# 2_waffling80-MX_matrix.net
KiCad netlist of a schematic drawn in Altium Designer
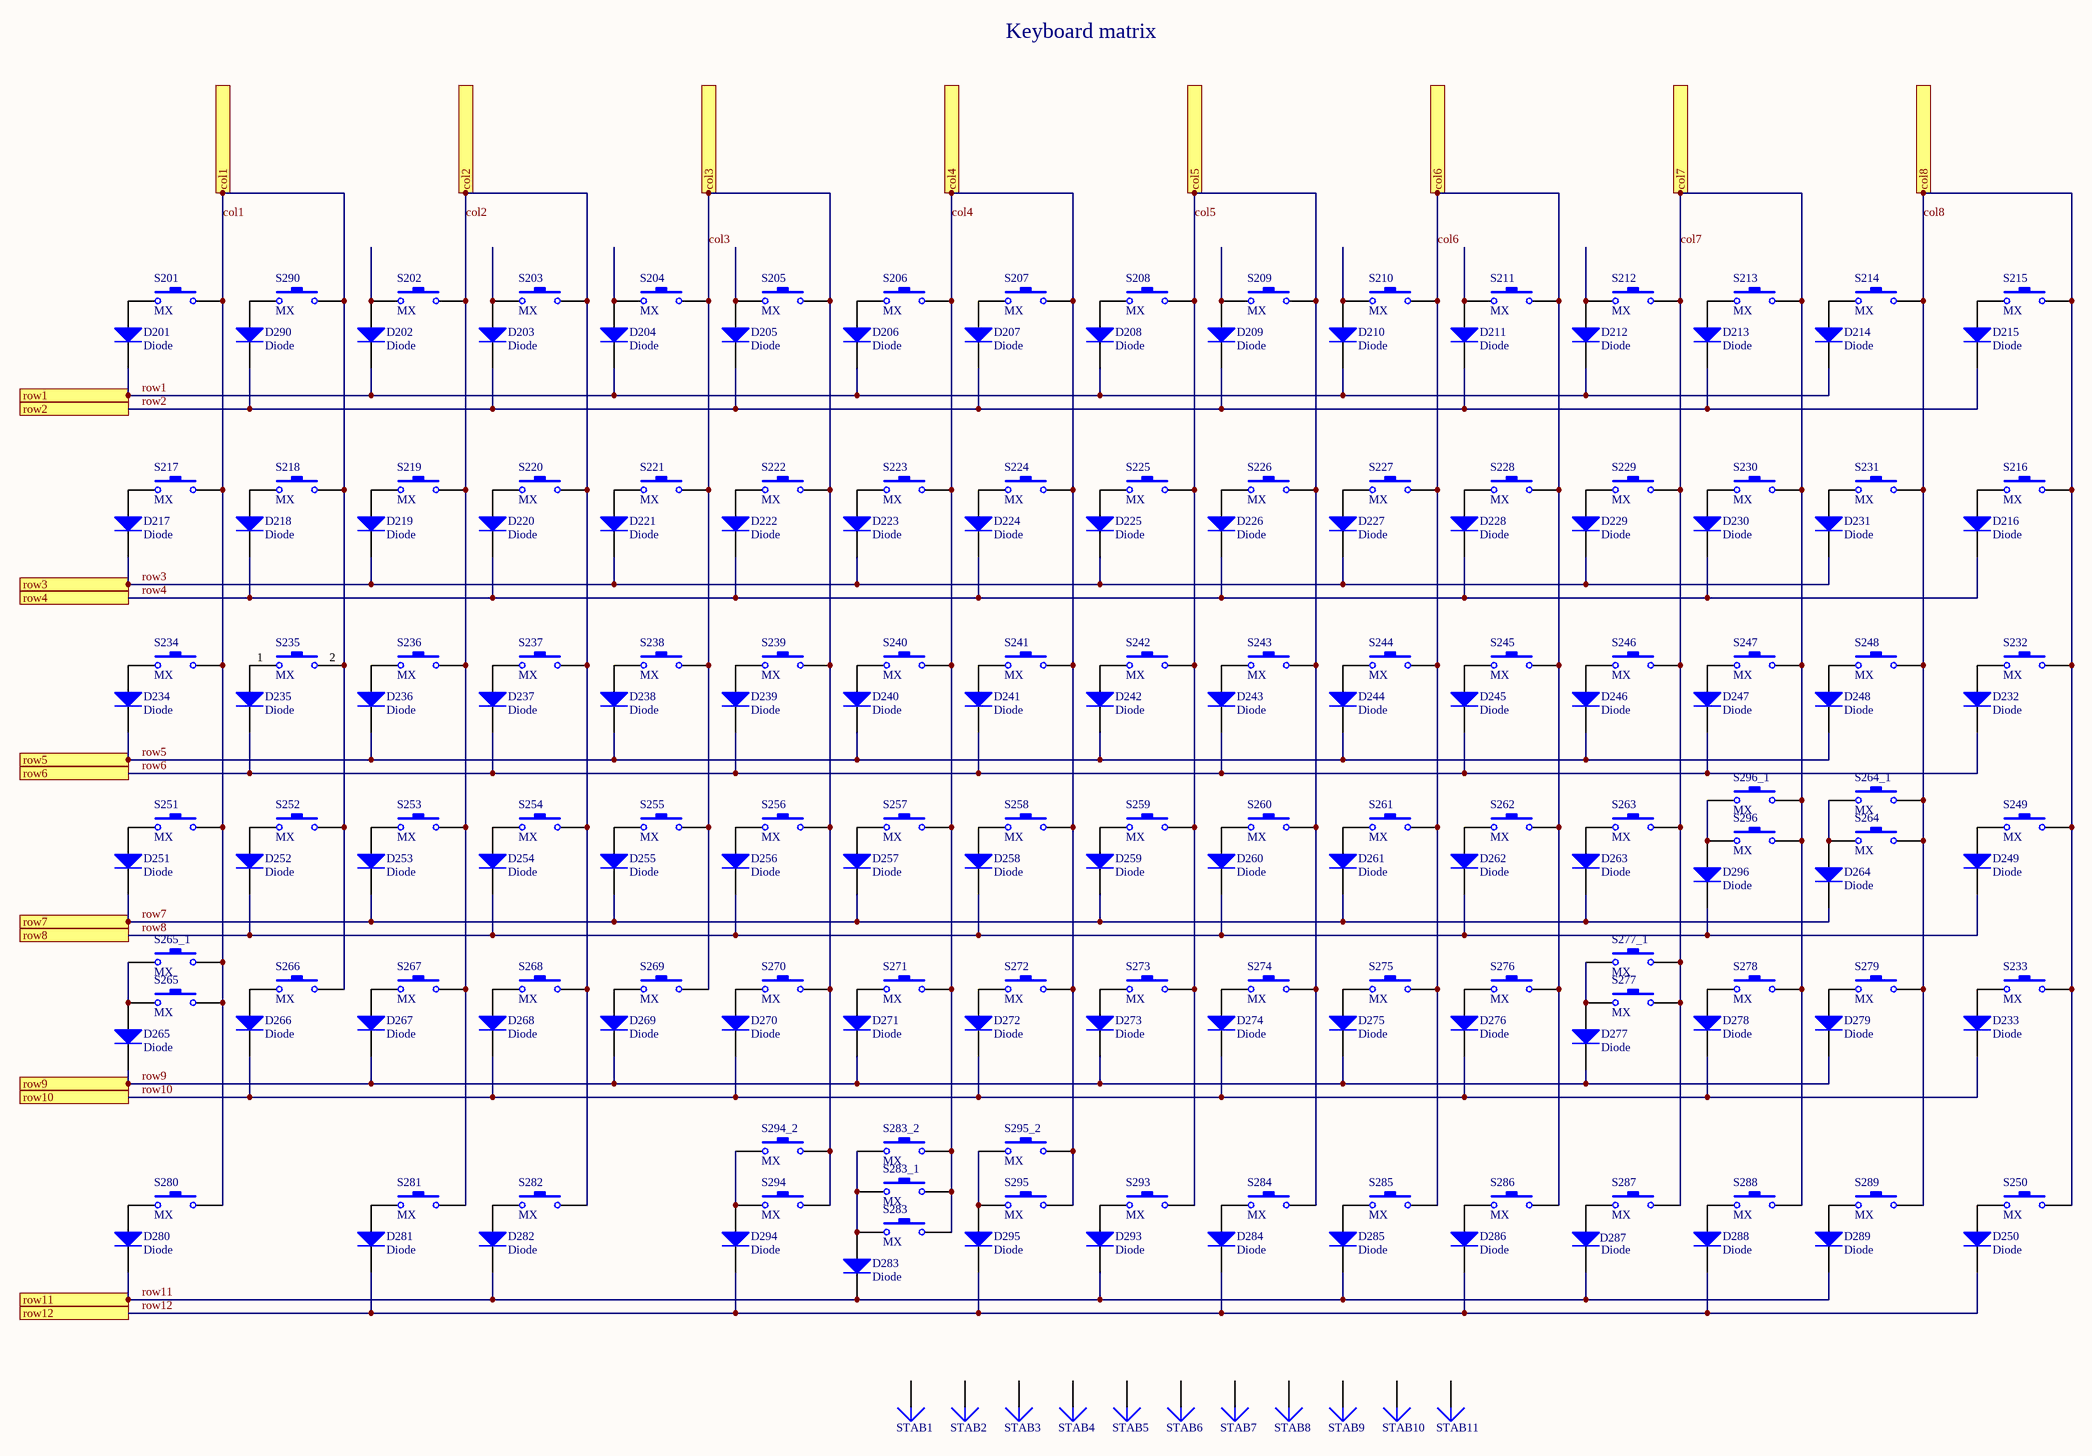
[diagram p0: 2_waffling80-MX_matrix.SchDoc]

(export (version "E")
  (design (tool "Eeschema 10.0.6"))
  (components
    (comp (ref "D201")
      (value "Diode")
      (footprint "SOD-123")
      (description "Default Diode")
      (fields (field (name "LCSC PART #") "C81598") (field (name "MRF.PART") "1N4148W"))
      (libsource (lib "Miscellaneous Devices") (part "Diode"))
    )
    (comp (ref "D202")
      (value "Diode")
      (footprint "SOD-123")
      (description "Default Diode")
      (fields (field (name "LCSC PART #") "C81598") (field (name "MRF.PART") "1N4148W"))
      (libsource (lib "Miscellaneous Devices") (part "Diode"))
    )
    (comp (ref "D203")
      (value "Diode")
      (footprint "SOD-123")
      (description "Default Diode")
      (fields (field (name "LCSC PART #") "C81598") (field (name "MRF.PART") "1N4148W"))
      (libsource (lib "Miscellaneous Devices") (part "Diode"))
    )
    (comp (ref "D204")
      (value "Diode")
      (footprint "SOD-123")
      (description "Default Diode")
      (fields (field (name "LCSC PART #") "C81598") (field (name "MRF.PART") "1N4148W"))
      (libsource (lib "Miscellaneous Devices") (part "Diode"))
    )
    (comp (ref "D205")
      (value "Diode")
      (footprint "SOD-123")
      (description "Default Diode")
      (fields (field (name "LCSC PART #") "C81598") (field (name "MRF.PART") "1N4148W"))
      (libsource (lib "Miscellaneous Devices") (part "Diode"))
    )
    (comp (ref "D206")
      (value "Diode")
      (footprint "SOD-123")
      (description "Default Diode")
      (fields (field (name "LCSC PART #") "C81598") (field (name "MRF.PART") "1N4148W"))
      (libsource (lib "Miscellaneous Devices") (part "Diode"))
    )
    (comp (ref "D207")
      (value "Diode")
      (footprint "SOD-123")
      (description "Default Diode")
      (fields (field (name "LCSC PART #") "C81598") (field (name "MRF.PART") "1N4148W"))
      (libsource (lib "Miscellaneous Devices") (part "Diode"))
    )
    (comp (ref "D208")
      (value "Diode")
      (footprint "SOD-123")
      (description "Default Diode")
      (fields (field (name "LCSC PART #") "C81598") (field (name "MRF.PART") "1N4148W"))
      (libsource (lib "Miscellaneous Devices") (part "Diode"))
    )
    (comp (ref "D209")
      (value "Diode")
      (footprint "SOD-123")
      (description "Default Diode")
      (fields (field (name "LCSC PART #") "C81598") (field (name "MRF.PART") "1N4148W"))
      (libsource (lib "Miscellaneous Devices") (part "Diode"))
    )
    (comp (ref "D210")
      (value "Diode")
      (footprint "SOD-123")
      (description "Default Diode")
      (fields (field (name "LCSC PART #") "C81598") (field (name "MRF.PART") "1N4148W"))
      (libsource (lib "Miscellaneous Devices") (part "Diode"))
    )
    (comp (ref "D211")
      (value "Diode")
      (footprint "SOD-123")
      (description "Default Diode")
      (fields (field (name "LCSC PART #") "C81598") (field (name "MRF.PART") "1N4148W"))
      (libsource (lib "Miscellaneous Devices") (part "Diode"))
    )
    (comp (ref "D212")
      (value "Diode")
      (footprint "SOD-123")
      (description "Default Diode")
      (fields (field (name "LCSC PART #") "C81598") (field (name "MRF.PART") "1N4148W"))
      (libsource (lib "Miscellaneous Devices") (part "Diode"))
    )
    (comp (ref "D213")
      (value "Diode")
      (footprint "SOD-123")
      (description "Default Diode")
      (fields (field (name "LCSC PART #") "C81598") (field (name "MRF.PART") "1N4148W"))
      (libsource (lib "Miscellaneous Devices") (part "Diode"))
    )
    (comp (ref "D214")
      (value "Diode")
      (footprint "SOD-123")
      (description "Default Diode")
      (fields (field (name "LCSC PART #") "C81598") (field (name "MRF.PART") "1N4148W"))
      (libsource (lib "Miscellaneous Devices") (part "Diode"))
    )
    (comp (ref "D215")
      (value "Diode")
      (footprint "SOD-123")
      (description "Default Diode")
      (fields (field (name "LCSC PART #") "C81598") (field (name "MRF.PART") "1N4148W"))
      (libsource (lib "Miscellaneous Devices") (part "Diode"))
    )
    (comp (ref "D216")
      (value "Diode")
      (footprint "SOD-123")
      (description "Default Diode")
      (fields (field (name "LCSC PART #") "C81598") (field (name "MRF.PART") "1N4148W"))
      (libsource (lib "Miscellaneous Devices") (part "Diode"))
    )
    (comp (ref "D217")
      (value "Diode")
      (footprint "SOD-123")
      (description "Default Diode")
      (fields (field (name "LCSC PART #") "C81598") (field (name "MRF.PART") "1N4148W"))
      (libsource (lib "Miscellaneous Devices") (part "Diode"))
    )
    (comp (ref "D218")
      (value "Diode")
      (footprint "SOD-123")
      (description "Default Diode")
      (fields (field (name "LCSC PART #") "C81598") (field (name "MRF.PART") "1N4148W"))
      (libsource (lib "Miscellaneous Devices") (part "Diode"))
    )
    (comp (ref "D219")
      (value "Diode")
      (footprint "SOD-123")
      (description "Default Diode")
      (fields (field (name "LCSC PART #") "C81598") (field (name "MRF.PART") "1N4148W"))
      (libsource (lib "Miscellaneous Devices") (part "Diode"))
    )
    (comp (ref "D220")
      (value "Diode")
      (footprint "SOD-123")
      (description "Default Diode")
      (fields (field (name "LCSC PART #") "C81598") (field (name "MRF.PART") "1N4148W"))
      (libsource (lib "Miscellaneous Devices") (part "Diode"))
    )
    (comp (ref "D221")
      (value "Diode")
      (footprint "SOD-123")
      (description "Default Diode")
      (fields (field (name "LCSC PART #") "C81598") (field (name "MRF.PART") "1N4148W"))
      (libsource (lib "Miscellaneous Devices") (part "Diode"))
    )
    (comp (ref "D222")
      (value "Diode")
      (footprint "SOD-123")
      (description "Default Diode")
      (fields (field (name "LCSC PART #") "C81598") (field (name "MRF.PART") "1N4148W"))
      (libsource (lib "Miscellaneous Devices") (part "Diode"))
    )
    (comp (ref "D223")
      (value "Diode")
      (footprint "SOD-123")
      (description "Default Diode")
      (fields (field (name "LCSC PART #") "C81598") (field (name "MRF.PART") "1N4148W"))
      (libsource (lib "Miscellaneous Devices") (part "Diode"))
    )
    (comp (ref "D224")
      (value "Diode")
      (footprint "SOD-123")
      (description "Default Diode")
      (fields (field (name "LCSC PART #") "C81598") (field (name "MRF.PART") "1N4148W"))
      (libsource (lib "Miscellaneous Devices") (part "Diode"))
    )
    (comp (ref "D225")
      (value "Diode")
      (footprint "SOD-123")
      (description "Default Diode")
      (fields (field (name "LCSC PART #") "C81598") (field (name "MRF.PART") "1N4148W"))
      (libsource (lib "Miscellaneous Devices") (part "Diode"))
    )
    (comp (ref "D226")
      (value "Diode")
      (footprint "SOD-123")
      (description "Default Diode")
      (fields (field (name "LCSC PART #") "C81598") (field (name "MRF.PART") "1N4148W"))
      (libsource (lib "Miscellaneous Devices") (part "Diode"))
    )
    (comp (ref "D227")
      (value "Diode")
      (footprint "SOD-123")
      (description "Default Diode")
      (fields (field (name "LCSC PART #") "C81598") (field (name "MRF.PART") "1N4148W"))
      (libsource (lib "Miscellaneous Devices") (part "Diode"))
    )
    (comp (ref "D228")
      (value "Diode")
      (footprint "SOD-123")
      (description "Default Diode")
      (fields (field (name "LCSC PART #") "C81598") (field (name "MRF.PART") "1N4148W"))
      (libsource (lib "Miscellaneous Devices") (part "Diode"))
    )
    (comp (ref "D229")
      (value "Diode")
      (footprint "SOD-123")
      (description "Default Diode")
      (fields (field (name "LCSC PART #") "C81598") (field (name "MRF.PART") "1N4148W"))
      (libsource (lib "Miscellaneous Devices") (part "Diode"))
    )
    (comp (ref "D230")
      (value "Diode")
      (footprint "SOD-123")
      (description "Default Diode")
      (fields (field (name "LCSC PART #") "C81598") (field (name "MRF.PART") "1N4148W"))
      (libsource (lib "Miscellaneous Devices") (part "Diode"))
    )
    (comp (ref "D231")
      (value "Diode")
      (footprint "SOD-123")
      (description "Default Diode")
      (fields (field (name "LCSC PART #") "C81598") (field (name "MRF.PART") "1N4148W"))
      (libsource (lib "Miscellaneous Devices") (part "Diode"))
    )
    (comp (ref "D232")
      (value "Diode")
      (footprint "SOD-123")
      (description "Default Diode")
      (fields (field (name "LCSC PART #") "C81598") (field (name "MRF.PART") "1N4148W"))
      (libsource (lib "Miscellaneous Devices") (part "Diode"))
    )
    (comp (ref "D233")
      (value "Diode")
      (footprint "SOD-123")
      (description "Default Diode")
      (fields (field (name "LCSC PART #") "C81598") (field (name "MRF.PART") "1N4148W"))
      (libsource (lib "Miscellaneous Devices") (part "Diode"))
    )
    (comp (ref "D234")
      (value "Diode")
      (footprint "SOD-123")
      (description "Default Diode")
      (fields (field (name "LCSC PART #") "C81598") (field (name "MRF.PART") "1N4148W"))
      (libsource (lib "Miscellaneous Devices") (part "Diode"))
    )
    (comp (ref "D235")
      (value "Diode")
      (footprint "SOD-123")
      (description "Default Diode")
      (fields (field (name "LCSC PART #") "C81598") (field (name "MRF.PART") "1N4148W"))
      (libsource (lib "Miscellaneous Devices") (part "Diode"))
    )
    (comp (ref "D236")
      (value "Diode")
      (footprint "SOD-123")
      (description "Default Diode")
      (fields (field (name "LCSC PART #") "C81598") (field (name "MRF.PART") "1N4148W"))
      (libsource (lib "Miscellaneous Devices") (part "Diode"))
    )
    (comp (ref "D237")
      (value "Diode")
      (footprint "SOD-123")
      (description "Default Diode")
      (fields (field (name "LCSC PART #") "C81598") (field (name "MRF.PART") "1N4148W"))
      (libsource (lib "Miscellaneous Devices") (part "Diode"))
    )
    (comp (ref "D238")
      (value "Diode")
      (footprint "SOD-123")
      (description "Default Diode")
      (fields (field (name "LCSC PART #") "C81598") (field (name "MRF.PART") "1N4148W"))
      (libsource (lib "Miscellaneous Devices") (part "Diode"))
    )
    (comp (ref "D239")
      (value "Diode")
      (footprint "SOD-123")
      (description "Default Diode")
      (fields (field (name "LCSC PART #") "C81598") (field (name "MRF.PART") "1N4148W"))
      (libsource (lib "Miscellaneous Devices") (part "Diode"))
    )
    (comp (ref "D240")
      (value "Diode")
      (footprint "SOD-123")
      (description "Default Diode")
      (fields (field (name "LCSC PART #") "C81598") (field (name "MRF.PART") "1N4148W"))
      (libsource (lib "Miscellaneous Devices") (part "Diode"))
    )
    (comp (ref "D241")
      (value "Diode")
      (footprint "SOD-123")
      (description "Default Diode")
      (fields (field (name "LCSC PART #") "C81598") (field (name "MRF.PART") "1N4148W"))
      (libsource (lib "Miscellaneous Devices") (part "Diode"))
    )
    (comp (ref "D242")
      (value "Diode")
      (footprint "SOD-123")
      (description "Default Diode")
      (fields (field (name "LCSC PART #") "C81598") (field (name "MRF.PART") "1N4148W"))
      (libsource (lib "Miscellaneous Devices") (part "Diode"))
    )
    (comp (ref "D243")
      (value "Diode")
      (footprint "SOD-123")
      (description "Default Diode")
      (fields (field (name "LCSC PART #") "C81598") (field (name "MRF.PART") "1N4148W"))
      (libsource (lib "Miscellaneous Devices") (part "Diode"))
    )
    (comp (ref "D244")
      (value "Diode")
      (footprint "SOD-123")
      (description "Default Diode")
      (fields (field (name "LCSC PART #") "C81598") (field (name "MRF.PART") "1N4148W"))
      (libsource (lib "Miscellaneous Devices") (part "Diode"))
    )
    (comp (ref "D245")
      (value "Diode")
      (footprint "SOD-123")
      (description "Default Diode")
      (fields (field (name "LCSC PART #") "C81598") (field (name "MRF.PART") "1N4148W"))
      (libsource (lib "Miscellaneous Devices") (part "Diode"))
    )
    (comp (ref "D246")
      (value "Diode")
      (footprint "SOD-123")
      (description "Default Diode")
      (fields (field (name "LCSC PART #") "C81598") (field (name "MRF.PART") "1N4148W"))
      (libsource (lib "Miscellaneous Devices") (part "Diode"))
    )
    (comp (ref "D247")
      (value "Diode")
      (footprint "SOD-123")
      (description "Default Diode")
      (fields (field (name "LCSC PART #") "C81598") (field (name "MRF.PART") "1N4148W"))
      (libsource (lib "Miscellaneous Devices") (part "Diode"))
    )
    (comp (ref "D248")
      (value "Diode")
      (footprint "SOD-123")
      (description "Default Diode")
      (fields (field (name "LCSC PART #") "C81598") (field (name "MRF.PART") "1N4148W"))
      (libsource (lib "Miscellaneous Devices") (part "Diode"))
    )
    (comp (ref "D249")
      (value "Diode")
      (footprint "SOD-123")
      (description "Default Diode")
      (fields (field (name "LCSC PART #") "C81598") (field (name "MRF.PART") "1N4148W"))
      (libsource (lib "Miscellaneous Devices") (part "Diode"))
    )
    (comp (ref "D250")
      (value "Diode")
      (footprint "SOD-123")
      (description "Default Diode")
      (fields (field (name "LCSC PART #") "C81598") (field (name "MRF.PART") "1N4148W"))
      (libsource (lib "Miscellaneous Devices") (part "Diode"))
    )
    (comp (ref "D251")
      (value "Diode")
      (footprint "SOD-123")
      (description "Default Diode")
      (fields (field (name "LCSC PART #") "C81598") (field (name "MRF.PART") "1N4148W"))
      (libsource (lib "Miscellaneous Devices") (part "Diode"))
    )
    (comp (ref "D252")
      (value "Diode")
      (footprint "SOD-123")
      (description "Default Diode")
      (fields (field (name "LCSC PART #") "C81598") (field (name "MRF.PART") "1N4148W"))
      (libsource (lib "Miscellaneous Devices") (part "Diode"))
    )
    (comp (ref "D253")
      (value "Diode")
      (footprint "SOD-123")
      (description "Default Diode")
      (fields (field (name "LCSC PART #") "C81598") (field (name "MRF.PART") "1N4148W"))
      (libsource (lib "Miscellaneous Devices") (part "Diode"))
    )
    (comp (ref "D254")
      (value "Diode")
      (footprint "SOD-123")
      (description "Default Diode")
      (fields (field (name "LCSC PART #") "C81598") (field (name "MRF.PART") "1N4148W"))
      (libsource (lib "Miscellaneous Devices") (part "Diode"))
    )
    (comp (ref "D255")
      (value "Diode")
      (footprint "SOD-123")
      (description "Default Diode")
      (fields (field (name "LCSC PART #") "C81598") (field (name "MRF.PART") "1N4148W"))
      (libsource (lib "Miscellaneous Devices") (part "Diode"))
    )
    (comp (ref "D256")
      (value "Diode")
      (footprint "SOD-123")
      (description "Default Diode")
      (fields (field (name "LCSC PART #") "C81598") (field (name "MRF.PART") "1N4148W"))
      (libsource (lib "Miscellaneous Devices") (part "Diode"))
    )
    (comp (ref "D257")
      (value "Diode")
      (footprint "SOD-123")
      (description "Default Diode")
      (fields (field (name "LCSC PART #") "C81598") (field (name "MRF.PART") "1N4148W"))
      (libsource (lib "Miscellaneous Devices") (part "Diode"))
    )
    (comp (ref "D258")
      (value "Diode")
      (footprint "SOD-123")
      (description "Default Diode")
      (fields (field (name "LCSC PART #") "C81598") (field (name "MRF.PART") "1N4148W"))
      (libsource (lib "Miscellaneous Devices") (part "Diode"))
    )
    (comp (ref "D259")
      (value "Diode")
      (footprint "SOD-123")
      (description "Default Diode")
      (fields (field (name "LCSC PART #") "C81598") (field (name "MRF.PART") "1N4148W"))
      (libsource (lib "Miscellaneous Devices") (part "Diode"))
    )
    (comp (ref "D260")
      (value "Diode")
      (footprint "SOD-123")
      (description "Default Diode")
      (fields (field (name "LCSC PART #") "C81598") (field (name "MRF.PART") "1N4148W"))
      (libsource (lib "Miscellaneous Devices") (part "Diode"))
    )
    (comp (ref "D261")
      (value "Diode")
      (footprint "SOD-123")
      (description "Default Diode")
      (fields (field (name "LCSC PART #") "C81598") (field (name "MRF.PART") "1N4148W"))
      (libsource (lib "Miscellaneous Devices") (part "Diode"))
    )
    (comp (ref "D262")
      (value "Diode")
      (footprint "SOD-123")
      (description "Default Diode")
      (fields (field (name "LCSC PART #") "C81598") (field (name "MRF.PART") "1N4148W"))
      (libsource (lib "Miscellaneous Devices") (part "Diode"))
    )
    (comp (ref "D263")
      (value "Diode")
      (footprint "SOD-123")
      (description "Default Diode")
      (fields (field (name "LCSC PART #") "C81598") (field (name "MRF.PART") "1N4148W"))
      (libsource (lib "Miscellaneous Devices") (part "Diode"))
    )
    (comp (ref "D264")
      (value "Diode")
      (footprint "SOD-123")
      (description "Default Diode")
      (fields (field (name "LCSC PART #") "C81598") (field (name "MRF.PART") "1N4148W"))
      (libsource (lib "Miscellaneous Devices") (part "Diode"))
    )
    (comp (ref "D265")
      (value "Diode")
      (footprint "SOD-123")
      (description "Default Diode")
      (fields (field (name "LCSC PART #") "C81598") (field (name "MRF.PART") "1N4148W"))
      (libsource (lib "Miscellaneous Devices") (part "Diode"))
    )
    (comp (ref "D266")
      (value "Diode")
      (footprint "SOD-123")
      (description "Default Diode")
      (fields (field (name "LCSC PART #") "C81598") (field (name "MRF.PART") "1N4148W"))
      (libsource (lib "Miscellaneous Devices") (part "Diode"))
    )
    (comp (ref "D267")
      (value "Diode")
      (footprint "SOD-123")
      (description "Default Diode")
      (fields (field (name "LCSC PART #") "C81598") (field (name "MRF.PART") "1N4148W"))
      (libsource (lib "Miscellaneous Devices") (part "Diode"))
    )
    (comp (ref "D268")
      (value "Diode")
      (footprint "SOD-123")
      (description "Default Diode")
      (fields (field (name "LCSC PART #") "C81598") (field (name "MRF.PART") "1N4148W"))
      (libsource (lib "Miscellaneous Devices") (part "Diode"))
    )
    (comp (ref "D269")
      (value "Diode")
      (footprint "SOD-123")
      (description "Default Diode")
      (fields (field (name "LCSC PART #") "C81598") (field (name "MRF.PART") "1N4148W"))
      (libsource (lib "Miscellaneous Devices") (part "Diode"))
    )
    (comp (ref "D270")
      (value "Diode")
      (footprint "SOD-123")
      (description "Default Diode")
      (fields (field (name "LCSC PART #") "C81598") (field (name "MRF.PART") "1N4148W"))
      (libsource (lib "Miscellaneous Devices") (part "Diode"))
    )
    (comp (ref "D271")
      (value "Diode")
      (footprint "SOD-123")
      (description "Default Diode")
      (fields (field (name "LCSC PART #") "C81598") (field (name "MRF.PART") "1N4148W"))
      (libsource (lib "Miscellaneous Devices") (part "Diode"))
    )
    (comp (ref "D272")
      (value "Diode")
      (footprint "SOD-123")
      (description "Default Diode")
      (fields (field (name "LCSC PART #") "C81598") (field (name "MRF.PART") "1N4148W"))
      (libsource (lib "Miscellaneous Devices") (part "Diode"))
    )
    (comp (ref "D273")
      (value "Diode")
      (footprint "SOD-123")
      (description "Default Diode")
      (fields (field (name "LCSC PART #") "C81598") (field (name "MRF.PART") "1N4148W"))
      (libsource (lib "Miscellaneous Devices") (part "Diode"))
    )
    (comp (ref "D274")
      (value "Diode")
      (footprint "SOD-123")
      (description "Default Diode")
      (fields (field (name "LCSC PART #") "C81598") (field (name "MRF.PART") "1N4148W"))
      (libsource (lib "Miscellaneous Devices") (part "Diode"))
    )
    (comp (ref "D275")
      (value "Diode")
      (footprint "SOD-123")
      (description "Default Diode")
      (fields (field (name "LCSC PART #") "C81598") (field (name "MRF.PART") "1N4148W"))
      (libsource (lib "Miscellaneous Devices") (part "Diode"))
    )
    (comp (ref "D276")
      (value "Diode")
      (footprint "SOD-123")
      (description "Default Diode")
      (fields (field (name "LCSC PART #") "C81598") (field (name "MRF.PART") "1N4148W"))
      (libsource (lib "Miscellaneous Devices") (part "Diode"))
    )
    (comp (ref "D277")
      (value "Diode")
      (footprint "SOD-123")
      (description "Default Diode")
      (fields (field (name "LCSC PART #") "C81598") (field (name "MRF.PART") "1N4148W"))
      (libsource (lib "Miscellaneous Devices") (part "Diode"))
    )
    (comp (ref "D278")
      (value "Diode")
      (footprint "SOD-123")
      (description "Default Diode")
      (fields (field (name "LCSC PART #") "C81598") (field (name "MRF.PART") "1N4148W"))
      (libsource (lib "Miscellaneous Devices") (part "Diode"))
    )
    (comp (ref "D279")
      (value "Diode")
      (footprint "SOD-123")
      (description "Default Diode")
      (fields (field (name "LCSC PART #") "C81598") (field (name "MRF.PART") "1N4148W"))
      (libsource (lib "Miscellaneous Devices") (part "Diode"))
    )
    (comp (ref "D280")
      (value "Diode")
      (footprint "SOD-123")
      (description "Default Diode")
      (fields (field (name "LCSC PART #") "C81598") (field (name "MRF.PART") "1N4148W"))
      (libsource (lib "Miscellaneous Devices") (part "Diode"))
    )
    (comp (ref "D281")
      (value "Diode")
      (footprint "SOD-123")
      (description "Default Diode")
      (fields (field (name "LCSC PART #") "C81598") (field (name "MRF.PART") "1N4148W"))
      (libsource (lib "Miscellaneous Devices") (part "Diode"))
    )
    (comp (ref "D282")
      (value "Diode")
      (footprint "SOD-123")
      (description "Default Diode")
      (fields (field (name "LCSC PART #") "C81598") (field (name "MRF.PART") "1N4148W"))
      (libsource (lib "Miscellaneous Devices") (part "Diode"))
    )
    (comp (ref "D283")
      (value "Diode")
      (footprint "SOD-123")
      (description "Default Diode")
      (fields (field (name "LCSC PART #") "C81598") (field (name "MRF.PART") "1N4148W"))
      (libsource (lib "Miscellaneous Devices") (part "Diode"))
    )
    (comp (ref "D284")
      (value "Diode")
      (footprint "SOD-123")
      (description "Default Diode")
      (fields (field (name "LCSC PART #") "C81598") (field (name "MRF.PART") "1N4148W"))
      (libsource (lib "Miscellaneous Devices") (part "Diode"))
    )
    (comp (ref "D285")
      (value "Diode")
      (footprint "SOD-123")
      (description "Default Diode")
      (fields (field (name "LCSC PART #") "C81598") (field (name "MRF.PART") "1N4148W"))
      (libsource (lib "Miscellaneous Devices") (part "Diode"))
    )
    (comp (ref "D286")
      (value "Diode")
      (footprint "SOD-123")
      (description "Default Diode")
      (fields (field (name "LCSC PART #") "C81598") (field (name "MRF.PART") "1N4148W"))
      (libsource (lib "Miscellaneous Devices") (part "Diode"))
    )
    (comp (ref "D287")
      (value "Diode")
      (footprint "SOD-123")
      (description "Default Diode")
      (fields (field (name "LCSC PART #") "C81598") (field (name "MRF.PART") "1N4148W"))
      (libsource (lib "Miscellaneous Devices") (part "Diode"))
    )
    (comp (ref "D288")
      (value "Diode")
      (footprint "SOD-123")
      (description "Default Diode")
      (fields (field (name "LCSC PART #") "C81598") (field (name "MRF.PART") "1N4148W"))
      (libsource (lib "Miscellaneous Devices") (part "Diode"))
    )
    (comp (ref "D289")
      (value "Diode")
      (footprint "SOD-123")
      (description "Default Diode")
      (fields (field (name "LCSC PART #") "C81598") (field (name "MRF.PART") "1N4148W"))
      (libsource (lib "Miscellaneous Devices") (part "Diode"))
    )
    (comp (ref "D290")
      (value "Diode")
      (footprint "SOD-123")
      (description "Default Diode")
      (fields (field (name "LCSC PART #") "C81598") (field (name "MRF.PART") "1N4148W"))
      (libsource (lib "Miscellaneous Devices") (part "Diode"))
    )
    (comp (ref "D293")
      (value "Diode")
      (footprint "SOD-123")
      (description "Default Diode")
      (fields (field (name "LCSC PART #") "C81598") (field (name "MRF.PART") "1N4148W"))
      (libsource (lib "Miscellaneous Devices") (part "Diode"))
    )
    (comp (ref "D294")
      (value "Diode")
      (footprint "SOD-123")
      (description "Default Diode")
      (fields (field (name "LCSC PART #") "C81598") (field (name "MRF.PART") "1N4148W"))
      (libsource (lib "Miscellaneous Devices") (part "Diode"))
    )
    (comp (ref "D295")
      (value "Diode")
      (footprint "SOD-123")
      (description "Default Diode")
      (fields (field (name "LCSC PART #") "C81598") (field (name "MRF.PART") "1N4148W"))
      (libsource (lib "Miscellaneous Devices") (part "Diode"))
    )
    (comp (ref "D296")
      (value "Diode")
      (footprint "SOD-123")
      (description "Default Diode")
      (fields (field (name "LCSC PART #") "C81598") (field (name "MRF.PART") "1N4148W"))
      (libsource (lib "Miscellaneous Devices") (part "Diode"))
    )
    (comp (ref "S201")
      (value "MX")
      (footprint "MX_ALPS-switch switched pol")
      (description "Switch")
      (libsource (lib "Miscellaneous Devices") (part "SW-PB"))
    )
    (comp (ref "S202")
      (value "MX")
      (footprint "MX_ALPS-switch switched pol")
      (description "Switch")
      (libsource (lib "Miscellaneous Devices") (part "SW-PB"))
    )
    (comp (ref "S203")
      (value "MX")
      (footprint "MX_ALPS-switch switched pol")
      (description "Switch")
      (libsource (lib "Miscellaneous Devices") (part "SW-PB"))
    )
    (comp (ref "S204")
      (value "MX")
      (footprint "MX_ALPS-switch switched pol")
      (description "Switch")
      (libsource (lib "Miscellaneous Devices") (part "SW-PB"))
    )
    (comp (ref "S205")
      (value "MX")
      (footprint "MX_ALPS-switch switched pol")
      (description "Switch")
      (libsource (lib "Miscellaneous Devices") (part "SW-PB"))
    )
    (comp (ref "S206")
      (value "MX")
      (footprint "MX_ALPS-switch")
      (description "Switch")
      (libsource (lib "Miscellaneous Devices") (part "SW-PB"))
    )
    (comp (ref "S207")
      (value "MX")
      (footprint "MX_ALPS-switch")
      (description "Switch")
      (libsource (lib "Miscellaneous Devices") (part "SW-PB"))
    )
    (comp (ref "S208")
      (value "MX")
      (footprint "MX_ALPS-switch")
      (description "Switch")
      (libsource (lib "Miscellaneous Devices") (part "SW-PB"))
    )
    (comp (ref "S209")
      (value "MX")
      (footprint "MX_ALPS-switch switched pol")
      (description "Switch")
      (libsource (lib "Miscellaneous Devices") (part "SW-PB"))
    )
    (comp (ref "S210")
      (value "MX")
      (footprint "MX_ALPS-switch")
      (description "Switch")
      (libsource (lib "Miscellaneous Devices") (part "SW-PB"))
    )
    (comp (ref "S211")
      (value "MX")
      (footprint "MX_ALPS-switch")
      (description "Switch")
      (libsource (lib "Miscellaneous Devices") (part "SW-PB"))
    )
    (comp (ref "S212")
      (value "MX")
      (footprint "MX_ALPS-switch")
      (description "Switch")
      (libsource (lib "Miscellaneous Devices") (part "SW-PB"))
    )
    (comp (ref "S213")
      (value "MX")
      (footprint "MX_ALPS-switch")
      (description "Switch")
      (libsource (lib "Miscellaneous Devices") (part "SW-PB"))
    )
    (comp (ref "S214")
      (value "MX")
      (footprint "MX_ALPS-switch switched pol")
      (description "Switch")
      (libsource (lib "Miscellaneous Devices") (part "SW-PB"))
    )
    (comp (ref "S215")
      (value "MX")
      (footprint "MX_ALPS-switch")
      (description "Switch")
      (libsource (lib "Miscellaneous Devices") (part "SW-PB"))
    )
    (comp (ref "S216")
      (value "MX")
      (footprint "MX_ALPS-switch")
      (description "Switch")
      (libsource (lib "Miscellaneous Devices") (part "SW-PB"))
    )
    (comp (ref "S217")
      (value "MX")
      (footprint "MX_ALPS-switch switched pol")
      (description "Switch")
      (libsource (lib "Miscellaneous Devices") (part "SW-PB"))
    )
    (comp (ref "S218")
      (value "MX")
      (footprint "MX_ALPS-switch switched pol")
      (description "Switch")
      (libsource (lib "Miscellaneous Devices") (part "SW-PB"))
    )
    (comp (ref "S219")
      (value "MX")
      (footprint "MX_ALPS-switch switched pol")
      (description "Switch")
      (libsource (lib "Miscellaneous Devices") (part "SW-PB"))
    )
    (comp (ref "S220")
      (value "MX")
      (footprint "MX_ALPS-switch switched pol")
      (description "Switch")
      (libsource (lib "Miscellaneous Devices") (part "SW-PB"))
    )
    (comp (ref "S221")
      (value "MX")
      (footprint "MX_ALPS-switch switched pol")
      (description "Switch")
      (libsource (lib "Miscellaneous Devices") (part "SW-PB"))
    )
    (comp (ref "S222")
      (value "MX")
      (footprint "MX_ALPS-switch switched pol")
      (description "Switch")
      (libsource (lib "Miscellaneous Devices") (part "SW-PB"))
    )
    (comp (ref "S223")
      (value "MX")
      (footprint "MX_ALPS-switch switched pol")
      (description "Switch")
      (libsource (lib "Miscellaneous Devices") (part "SW-PB"))
    )
    (comp (ref "S224")
      (value "MX")
      (footprint "MX_ALPS-switch switched pol")
      (description "Switch")
      (libsource (lib "Miscellaneous Devices") (part "SW-PB"))
    )
    (comp (ref "S225")
      (value "MX")
      (footprint "MX_ALPS-switch switched pol")
      (description "Switch")
      (libsource (lib "Miscellaneous Devices") (part "SW-PB"))
    )
    (comp (ref "S226")
      (value "MX")
      (footprint "MX_ALPS-switch switched pol")
      (description "Switch")
      (libsource (lib "Miscellaneous Devices") (part "SW-PB"))
    )
    (comp (ref "S227")
      (value "MX")
      (footprint "MX_ALPS-switch switched pol")
      (description "Switch")
      (libsource (lib "Miscellaneous Devices") (part "SW-PB"))
    )
    (comp (ref "S228")
      (value "MX")
      (footprint "MX_ALPS-switch switched pol")
      (description "Switch")
      (libsource (lib "Miscellaneous Devices") (part "SW-PB"))
    )
    (comp (ref "S229")
      (value "MX")
      (footprint "MX_ALPS-switch switched pol")
      (description "Switch")
      (libsource (lib "Miscellaneous Devices") (part "SW-PB"))
    )
    (comp (ref "S230")
      (value "MX")
      (footprint "MX_ALPS-switch")
      (description "Switch")
      (libsource (lib "Miscellaneous Devices") (part "SW-PB"))
    )
    (comp (ref "S231")
      (value "MX")
      (footprint "MX_ALPS-switch")
      (description "Switch")
      (libsource (lib "Miscellaneous Devices") (part "SW-PB"))
    )
    (comp (ref "S232")
      (value "MX")
      (footprint "MX_ALPS-switch")
      (description "Switch")
      (libsource (lib "Miscellaneous Devices") (part "SW-PB"))
    )
    (comp (ref "S233")
      (value "MX")
      (footprint "MX_ALPS-switch")
      (description "Switch")
      (libsource (lib "Miscellaneous Devices") (part "SW-PB"))
    )
    (comp (ref "S234")
      (value "MX")
      (footprint "MX_ALPS-switch switched pol")
      (description "TAB")
      (libsource (lib "Miscellaneous Devices") (part "SW-PB"))
    )
    (comp (ref "S235")
      (value "MX")
      (footprint "MX_ALPS-switch switched pol")
      (description "Switch")
      (libsource (lib "") (part "SW-PB_1"))
    )
    (comp (ref "S236")
      (value "MX")
      (footprint "MX_ALPS-switch switched pol")
      (description "Switch")
      (libsource (lib "Miscellaneous Devices") (part "SW-PB"))
    )
    (comp (ref "S237")
      (value "MX")
      (footprint "MX_ALPS-switch switched pol")
      (description "Switch")
      (libsource (lib "Miscellaneous Devices") (part "SW-PB"))
    )
    (comp (ref "S238")
      (value "MX")
      (footprint "MX_ALPS-switch switched pol")
      (description "Switch")
      (libsource (lib "Miscellaneous Devices") (part "SW-PB"))
    )
    (comp (ref "S239")
      (value "MX")
      (footprint "MX_ALPS-switch switched pol")
      (description "Switch")
      (libsource (lib "Miscellaneous Devices") (part "SW-PB"))
    )
    (comp (ref "S240")
      (value "MX")
      (footprint "MX_ALPS-switch switched pol")
      (description "Switch")
      (libsource (lib "Miscellaneous Devices") (part "SW-PB"))
    )
    (comp (ref "S241")
      (value "MX")
      (footprint "MX_ALPS-switch switched pol")
      (description "Switch")
      (libsource (lib "Miscellaneous Devices") (part "SW-PB"))
    )
    (comp (ref "S242")
      (value "MX")
      (footprint "MX_ALPS-switch switched pol")
      (description "Switch")
      (libsource (lib "Miscellaneous Devices") (part "SW-PB"))
    )
    (comp (ref "S243")
      (value "MX")
      (footprint "MX_ALPS-switch switched pol")
      (description "Switch")
      (libsource (lib "Miscellaneous Devices") (part "SW-PB"))
    )
    (comp (ref "S244")
      (value "MX")
      (footprint "MX_ALPS-switch switched pol")
      (description "Switch")
      (libsource (lib "Miscellaneous Devices") (part "SW-PB"))
    )
    (comp (ref "S245")
      (value "MX")
      (footprint "MX_ALPS-switch switched pol")
      (description "Switch")
      (libsource (lib "Miscellaneous Devices") (part "SW-PB"))
    )
    (comp (ref "S246")
      (value "MX")
      (footprint "MX_ALPS-switch switched pol")
      (description "Switch")
      (libsource (lib "Miscellaneous Devices") (part "SW-PB"))
    )
    (comp (ref "S247")
      (value "MX")
      (footprint "mx_alps - 1.5U")
      (description "Switch")
      (libsource (lib "Miscellaneous Devices") (part "SW-PB"))
    )
    (comp (ref "S248")
      (value "MX")
      (footprint "MX_ALPS-switch")
      (description "Switch")
      (libsource (lib "Miscellaneous Devices") (part "SW-PB"))
    )
    (comp (ref "S249")
      (value "MX")
      (footprint "MX_ALPS-switch")
      (description "Switch")
      (libsource (lib "Miscellaneous Devices") (part "SW-PB"))
    )
    (comp (ref "S250")
      (value "MX")
      (footprint "MX_ALPS-switch")
      (description "Switch")
      (libsource (lib "Miscellaneous Devices") (part "SW-PB"))
    )
    (comp (ref "S251")
      (value "MX")
      (footprint "mx_alps - CAPS")
      (description "Switch")
      (libsource (lib "Miscellaneous Devices") (part "SW-PB"))
    )
    (comp (ref "S252")
      (value "MX")
      (footprint "MX_ALPS-switch switched pol")
      (description "Switch")
      (libsource (lib "Miscellaneous Devices") (part "SW-PB"))
    )
    (comp (ref "S253")
      (value "MX")
      (footprint "MX_ALPS-switch switched pol")
      (description "Switch")
      (libsource (lib "Miscellaneous Devices") (part "SW-PB"))
    )
    (comp (ref "S254")
      (value "MX")
      (footprint "MX_ALPS-switch switched pol")
      (description "Switch")
      (libsource (lib "Miscellaneous Devices") (part "SW-PB"))
    )
    (comp (ref "S255")
      (value "MX")
      (footprint "MX_ALPS-switch switched pol")
      (description "Switch")
      (libsource (lib "Miscellaneous Devices") (part "SW-PB"))
    )
    (comp (ref "S256")
      (value "MX")
      (footprint "MX_ALPS-switch switched pol")
      (description "Switch")
      (libsource (lib "Miscellaneous Devices") (part "SW-PB"))
    )
    (comp (ref "S257")
      (value "MX")
      (footprint "MX_ALPS-switch switched pol")
      (description "Switch")
      (libsource (lib "Miscellaneous Devices") (part "SW-PB"))
    )
    (comp (ref "S258")
      (value "MX")
      (footprint "MX_ALPS-switch switched pol")
      (description "Switch")
      (libsource (lib "Miscellaneous Devices") (part "SW-PB"))
    )
    (comp (ref "S259")
      (value "MX")
      (footprint "MX_ALPS-switch switched pol")
      (description "Switch")
      (libsource (lib "Miscellaneous Devices") (part "SW-PB"))
    )
    (comp (ref "S260")
      (value "MX")
      (footprint "MX_ALPS-switch switched pol")
      (description "Switch")
      (libsource (lib "Miscellaneous Devices") (part "SW-PB"))
    )
    (comp (ref "S261")
      (value "MX")
      (footprint "MX_ALPS-switch")
      (description "Switch")
      (libsource (lib "Miscellaneous Devices") (part "SW-PB"))
    )
    (comp (ref "S262")
      (value "MX")
      (footprint "MX_ALPS-switch switched pol")
      (description "Switch")
      (libsource (lib "Miscellaneous Devices") (part "SW-PB"))
    )
    (comp (ref "S263")
      (value "MX")
      (footprint "MX_ALPS-switch")
      (description "Switch")
      (libsource (lib "Miscellaneous Devices") (part "SW-PB"))
    )
    (comp (ref "S264")
      (value "MX")
      (footprint "MX_ALPS-switch switched pol")
      (description "Switch")
      (libsource (lib "Miscellaneous Devices") (part "SW-PB"))
    )
    (comp (ref "S264_1")
      (value "MX")
      (footprint "MX_ALPS-switch")
      (description "Switch")
      (libsource (lib "Miscellaneous Devices") (part "SW-PB"))
    )
    (comp (ref "S265")
      (value "MX")
      (footprint "MX_ALPS-switch switched pol")
      (description "Switch")
      (libsource (lib "Miscellaneous Devices") (part "SW-PB"))
    )
    (comp (ref "S265_1")
      (value "MX")
      (footprint "MX_ALPS-switch")
      (description "Switch")
      (libsource (lib "Miscellaneous Devices") (part "SW-PB"))
    )
    (comp (ref "S266")
      (value "MX")
      (footprint "MX_ALPS-switch switched pol")
      (description "Switch")
      (libsource (lib "Miscellaneous Devices") (part "SW-PB"))
    )
    (comp (ref "S267")
      (value "MX")
      (footprint "MX_ALPS-switch switched pol")
      (description "Switch")
      (libsource (lib "Miscellaneous Devices") (part "SW-PB"))
    )
    (comp (ref "S268")
      (value "MX")
      (footprint "MX_ALPS-switch switched pol")
      (description "Switch")
      (libsource (lib "Miscellaneous Devices") (part "SW-PB"))
    )
    (comp (ref "S269")
      (value "MX")
      (footprint "MX_ALPS-switch switched pol")
      (description "Switch")
      (libsource (lib "Miscellaneous Devices") (part "SW-PB"))
    )
    (comp (ref "S270")
      (value "MX")
      (footprint "MX_ALPS-switch switched pol")
      (description "Switch")
      (libsource (lib "Miscellaneous Devices") (part "SW-PB"))
    )
    (comp (ref "S271")
      (value "MX")
      (footprint "MX_ALPS-switch switched pol")
      (description "Switch")
      (libsource (lib "Miscellaneous Devices") (part "SW-PB"))
    )
    (comp (ref "S272")
      (value "MX")
      (footprint "MX_ALPS-switch switched pol")
      (description "Switch")
      (libsource (lib "Miscellaneous Devices") (part "SW-PB"))
    )
    (comp (ref "S273")
      (value "MX")
      (footprint "MX_ALPS-switch switched pol")
      (description "Switch")
      (libsource (lib "Miscellaneous Devices") (part "SW-PB"))
    )
    (comp (ref "S274")
      (value "MX")
      (footprint "MX_ALPS-switch switched pol")
      (description "Switch")
      (libsource (lib "Miscellaneous Devices") (part "SW-PB"))
    )
    (comp (ref "S275")
      (value "MX")
      (footprint "MX_ALPS-switch switched pol")
      (description "Switch")
      (libsource (lib "Miscellaneous Devices") (part "SW-PB"))
    )
    (comp (ref "S276")
      (value "MX")
      (footprint "MX_ALPS-switch switched pol")
      (description "Switch")
      (libsource (lib "Miscellaneous Devices") (part "SW-PB"))
    )
    (comp (ref "S277")
      (value "MX")
      (footprint "MX_ALPS-switch switched pol")
      (description "Switch")
      (libsource (lib "Miscellaneous Devices") (part "SW-PB"))
    )
    (comp (ref "S277_1")
      (value "MX")
      (footprint "MX_ALPS-switch")
      (description "Switch")
      (libsource (lib "Miscellaneous Devices") (part "SW-PB"))
    )
    (comp (ref "S278")
      (value "MX")
      (footprint "MX_ALPS-switch switched pol")
      (description "Switch")
      (libsource (lib "Miscellaneous Devices") (part "SW-PB"))
    )
    (comp (ref "S279")
      (value "MX")
      (footprint "MX_ALPS-switch")
      (description "Switch")
      (libsource (lib "Miscellaneous Devices") (part "SW-PB"))
    )
    (comp (ref "S280")
      (value "MX")
      (footprint "mx_alps- 1.5u MOD-L")
      (description "Switch")
      (libsource (lib "Miscellaneous Devices") (part "SW-PB"))
    )
    (comp (ref "S281")
      (value "MX")
      (footprint "mx_alps - 1u MOD-L")
      (description "Switch")
      (libsource (lib "Miscellaneous Devices") (part "SW-PB"))
    )
    (comp (ref "S282")
      (value "MX")
      (footprint "mx_alps- 1.5u MOD-L")
      (description "Switch")
      (libsource (lib "Miscellaneous Devices") (part "SW-PB"))
    )
    (comp (ref "S283")
      (value "MX")
      (footprint "MX_ALPS-switch")
      (description "Switch")
      (libsource (lib "Miscellaneous Devices") (part "SW-PB"))
    )
    (comp (ref "S283_1")
      (value "MX")
      (footprint "MX_ALPS-switch")
      (description "Switch")
      (libsource (lib "Miscellaneous Devices") (part "SW-PB"))
    )
    (comp (ref "S283_2")
      (value "MX")
      (footprint "MX_ALPS-switch switched pol")
      (description "Switch")
      (libsource (lib "Miscellaneous Devices") (part "SW-PB"))
    )
    (comp (ref "S284")
      (value "MX")
      (footprint "mx_alps - 1.5u MOD-R")
      (description "Switch")
      (libsource (lib "Miscellaneous Devices") (part "SW-PB"))
    )
    (comp (ref "S285")
      (value "MX")
      (footprint "mx_alps - 1u MOD-R")
      (description "Switch")
      (libsource (lib "Miscellaneous Devices") (part "SW-PB"))
    )
    (comp (ref "S286")
      (value "MX")
      (footprint "mx_alps - 1.5u MOD-R")
      (description "Switch")
      (libsource (lib "Miscellaneous Devices") (part "SW-PB"))
    )
    (comp (ref "S287")
      (value "MX")
      (footprint "MX_ALPS-switch")
      (description "Switch")
      (libsource (lib "Miscellaneous Devices") (part "SW-PB"))
    )
    (comp (ref "S288")
      (value "MX")
      (footprint "MX_ALPS-switch")
      (description "Switch")
      (libsource (lib "Miscellaneous Devices") (part "SW-PB"))
    )
    (comp (ref "S289")
      (value "MX")
      (footprint "MX_ALPS-switch")
      (description "Switch")
      (libsource (lib "Miscellaneous Devices") (part "SW-PB"))
    )
    (comp (ref "S290")
      (value "MX")
      (footprint "MX_ALPS-switch")
      (description "Switch")
      (libsource (lib "Miscellaneous Devices") (part "SW-PB"))
    )
    (comp (ref "S293")
      (value "MX")
      (footprint "MX_ALPS-switch")
      (description "Switch")
      (libsource (lib "Miscellaneous Devices") (part "SW-PB"))
    )
    (comp (ref "S294")
      (value "MX")
      (footprint "MX_ALPS-switch")
      (description "Switch")
      (libsource (lib "Miscellaneous Devices") (part "SW-PB"))
    )
    (comp (ref "S294_2")
      (value "MX")
      (footprint "MX_ALPS-switch")
      (description "Switch")
      (libsource (lib "Miscellaneous Devices") (part "SW-PB"))
    )
    (comp (ref "S295")
      (value "MX")
      (footprint "MX_ALPS-switch")
      (description "Switch")
      (libsource (lib "Miscellaneous Devices") (part "SW-PB"))
    )
    (comp (ref "S295_2")
      (value "MX")
      (footprint "MX_ALPS-switch")
      (description "Switch")
      (libsource (lib "Miscellaneous Devices") (part "SW-PB"))
    )
    (comp (ref "S296")
      (value "MX")
      (footprint "MX_ALPS-switch switched pol")
      (description "Switch")
      (libsource (lib "Miscellaneous Devices") (part "SW-PB"))
    )
    (comp (ref "S296_1")
      (value "MX")
      (footprint "mx_alps-switch")
      (description "Switch")
      (libsource (lib "Miscellaneous Devices") (part "SW-PB"))
    )
    (comp (ref "STAB1")
      (value "Plug")
      (footprint "Stab 2u")
      (libsource (lib "Miscellaneous Connectors") (part "Plug"))
    )
    (comp (ref "STAB2")
      (value "Plug")
      (footprint "Stab 2u")
      (libsource (lib "Miscellaneous Connectors") (part "Plug"))
    )
    (comp (ref "STAB3")
      (value "Plug")
      (footprint "Stab 2u")
      (libsource (lib "Miscellaneous Connectors") (part "Plug"))
    )
    (comp (ref "STAB4")
      (value "Plug")
      (footprint "Stab 2u")
      (libsource (lib "Miscellaneous Connectors") (part "Plug"))
    )
    (comp (ref "STAB5")
      (value "Plug")
      (footprint "Stab 2u")
      (libsource (lib "Miscellaneous Connectors") (part "Plug"))
    )
    (comp (ref "STAB6")
      (value "Plug")
      (footprint "Stab 6.25U")
      (libsource (lib "Miscellaneous Connectors") (part "Plug"))
    )
    (comp (ref "STAB7")
      (value "Plug")
      (footprint "Stab 7U")
      (libsource (lib "Miscellaneous Connectors") (part "Plug"))
    )
    (comp (ref "STAB8")
      (value "Plug")
      (footprint "Stab 2u")
      (libsource (lib "Miscellaneous Connectors") (part "Plug"))
    )
    (comp (ref "STAB9")
      (value "Plug")
      (footprint "Stab 3u")
      (libsource (lib "Miscellaneous Connectors") (part "Plug"))
    )
    (comp (ref "STAB10")
      (value "Plug")
      (footprint "Stab 3u")
      (libsource (lib "Miscellaneous Connectors") (part "Plug"))
    )
    (comp (ref "STAB11")
      (value "Plug")
      (footprint "Stab 2u")
      (libsource (lib "Miscellaneous Connectors") (part "Plug"))
    )
  )
  (nets
    (net (code "1") (name "/col1") (class "Default")
      (node (ref "S201") (pin "2") (pinfunction "2_2") (pintype "passive"))
      (node (ref "S217") (pin "2") (pinfunction "2_2") (pintype "passive"))
      (node (ref "S218") (pin "2") (pinfunction "2_2") (pintype "passive"))
      (node (ref "S234") (pin "2") (pinfunction "2_2") (pintype "passive"))
      (node (ref "S235") (pin "2") (pinfunction "2_2") (pintype "passive"))
      (node (ref "S251") (pin "2") (pinfunction "2_2") (pintype "passive"))
      (node (ref "S252") (pin "2") (pinfunction "2_2") (pintype "passive"))
      (node (ref "S265") (pin "2") (pinfunction "2_2") (pintype "passive"))
      (node (ref "S265_1") (pin "2") (pinfunction "2_2") (pintype "passive"))
      (node (ref "S266") (pin "2") (pinfunction "2_2") (pintype "passive"))
      (node (ref "S280") (pin "1") (pinfunction "1_1") (pintype "passive"))
      (node (ref "S290") (pin "2") (pinfunction "2_2") (pintype "passive"))
    )
    (net (code "2") (name "/col2") (class "Default")
      (node (ref "S202") (pin "2") (pinfunction "2_2") (pintype "passive"))
      (node (ref "S203") (pin "2") (pinfunction "2_2") (pintype "passive"))
      (node (ref "S219") (pin "2") (pinfunction "2_2") (pintype "passive"))
      (node (ref "S220") (pin "2") (pinfunction "2_2") (pintype "passive"))
      (node (ref "S236") (pin "2") (pinfunction "2_2") (pintype "passive"))
      (node (ref "S237") (pin "2") (pinfunction "2_2") (pintype "passive"))
      (node (ref "S253") (pin "2") (pinfunction "2_2") (pintype "passive"))
      (node (ref "S254") (pin "2") (pinfunction "2_2") (pintype "passive"))
      (node (ref "S267") (pin "2") (pinfunction "2_2") (pintype "passive"))
      (node (ref "S268") (pin "2") (pinfunction "2_2") (pintype "passive"))
      (node (ref "S281") (pin "1") (pinfunction "1_1") (pintype "passive"))
      (node (ref "S282") (pin "1") (pinfunction "1_1") (pintype "passive"))
    )
    (net (code "3") (name "/col3") (class "Default")
      (node (ref "S204") (pin "2") (pinfunction "2_2") (pintype "passive"))
      (node (ref "S205") (pin "2") (pinfunction "2_2") (pintype "passive"))
      (node (ref "S221") (pin "2") (pinfunction "2_2") (pintype "passive"))
      (node (ref "S222") (pin "2") (pinfunction "2_2") (pintype "passive"))
      (node (ref "S238") (pin "2") (pinfunction "2_2") (pintype "passive"))
      (node (ref "S239") (pin "2") (pinfunction "2_2") (pintype "passive"))
      (node (ref "S255") (pin "2") (pinfunction "2_2") (pintype "passive"))
      (node (ref "S256") (pin "2") (pinfunction "2_2") (pintype "passive"))
      (node (ref "S269") (pin "2") (pinfunction "2_2") (pintype "passive"))
      (node (ref "S270") (pin "2") (pinfunction "2_2") (pintype "passive"))
      (node (ref "S294") (pin "1") (pinfunction "1_1") (pintype "passive"))
      (node (ref "S294_2") (pin "2") (pinfunction "2_2") (pintype "passive"))
    )
    (net (code "4") (name "/col4") (class "Default")
      (node (ref "S206") (pin "2") (pinfunction "2_2") (pintype "passive"))
      (node (ref "S207") (pin "2") (pinfunction "2_2") (pintype "passive"))
      (node (ref "S223") (pin "2") (pinfunction "2_2") (pintype "passive"))
      (node (ref "S224") (pin "2") (pinfunction "2_2") (pintype "passive"))
      (node (ref "S240") (pin "2") (pinfunction "2_2") (pintype "passive"))
      (node (ref "S241") (pin "2") (pinfunction "2_2") (pintype "passive"))
      (node (ref "S257") (pin "2") (pinfunction "2_2") (pintype "passive"))
      (node (ref "S258") (pin "2") (pinfunction "2_2") (pintype "passive"))
      (node (ref "S271") (pin "2") (pinfunction "2_2") (pintype "passive"))
      (node (ref "S272") (pin "2") (pinfunction "2_2") (pintype "passive"))
      (node (ref "S283") (pin "2") (pinfunction "2_2") (pintype "passive"))
      (node (ref "S283_1") (pin "2") (pinfunction "2_2") (pintype "passive"))
      (node (ref "S283_2") (pin "2") (pinfunction "2_2") (pintype "passive"))
      (node (ref "S295") (pin "1") (pinfunction "1_1") (pintype "passive"))
      (node (ref "S295_2") (pin "2") (pinfunction "2_2") (pintype "passive"))
    )
    (net (code "5") (name "/col5") (class "Default")
      (node (ref "S208") (pin "2") (pinfunction "2_2") (pintype "passive"))
      (node (ref "S209") (pin "2") (pinfunction "2_2") (pintype "passive"))
      (node (ref "S225") (pin "2") (pinfunction "2_2") (pintype "passive"))
      (node (ref "S226") (pin "2") (pinfunction "2_2") (pintype "passive"))
      (node (ref "S242") (pin "2") (pinfunction "2_2") (pintype "passive"))
      (node (ref "S243") (pin "2") (pinfunction "2_2") (pintype "passive"))
      (node (ref "S259") (pin "2") (pinfunction "2_2") (pintype "passive"))
      (node (ref "S260") (pin "2") (pinfunction "2_2") (pintype "passive"))
      (node (ref "S273") (pin "2") (pinfunction "2_2") (pintype "passive"))
      (node (ref "S274") (pin "2") (pinfunction "2_2") (pintype "passive"))
      (node (ref "S284") (pin "2") (pinfunction "2_2") (pintype "passive"))
      (node (ref "S293") (pin "2") (pinfunction "2_2") (pintype "passive"))
    )
    (net (code "6") (name "/col6") (class "Default")
      (node (ref "S210") (pin "2") (pinfunction "2_2") (pintype "passive"))
      (node (ref "S211") (pin "2") (pinfunction "2_2") (pintype "passive"))
      (node (ref "S227") (pin "2") (pinfunction "2_2") (pintype "passive"))
      (node (ref "S228") (pin "2") (pinfunction "2_2") (pintype "passive"))
      (node (ref "S244") (pin "2") (pinfunction "2_2") (pintype "passive"))
      (node (ref "S245") (pin "2") (pinfunction "2_2") (pintype "passive"))
      (node (ref "S261") (pin "2") (pinfunction "2_2") (pintype "passive"))
      (node (ref "S262") (pin "2") (pinfunction "2_2") (pintype "passive"))
      (node (ref "S275") (pin "2") (pinfunction "2_2") (pintype "passive"))
      (node (ref "S276") (pin "2") (pinfunction "2_2") (pintype "passive"))
      (node (ref "S285") (pin "2") (pinfunction "2_2") (pintype "passive"))
      (node (ref "S286") (pin "2") (pinfunction "2_2") (pintype "passive"))
    )
    (net (code "7") (name "/col7") (class "Default")
      (node (ref "S212") (pin "2") (pinfunction "2_2") (pintype "passive"))
      (node (ref "S213") (pin "2") (pinfunction "2_2") (pintype "passive"))
      (node (ref "S229") (pin "2") (pinfunction "2_2") (pintype "passive"))
      (node (ref "S230") (pin "2") (pinfunction "2_2") (pintype "passive"))
      (node (ref "S246") (pin "2") (pinfunction "2_2") (pintype "passive"))
      (node (ref "S247") (pin "2") (pinfunction "2_2") (pintype "passive"))
      (node (ref "S263") (pin "2") (pinfunction "2_2") (pintype "passive"))
      (node (ref "S277") (pin "2") (pinfunction "2_2") (pintype "passive"))
      (node (ref "S277_1") (pin "2") (pinfunction "2_2") (pintype "passive"))
      (node (ref "S278") (pin "2") (pinfunction "2_2") (pintype "passive"))
      (node (ref "S287") (pin "2") (pinfunction "2_2") (pintype "passive"))
      (node (ref "S288") (pin "2") (pinfunction "2_2") (pintype "passive"))
      (node (ref "S296") (pin "2") (pinfunction "2_2") (pintype "passive"))
      (node (ref "S296_1") (pin "2") (pinfunction "2_2") (pintype "passive"))
    )
    (net (code "8") (name "/col8") (class "Default")
      (node (ref "S214") (pin "2") (pinfunction "2_2") (pintype "passive"))
      (node (ref "S215") (pin "2") (pinfunction "2_2") (pintype "passive"))
      (node (ref "S216") (pin "2") (pinfunction "2_2") (pintype "passive"))
      (node (ref "S231") (pin "2") (pinfunction "2_2") (pintype "passive"))
      (node (ref "S232") (pin "2") (pinfunction "2_2") (pintype "passive"))
      (node (ref "S233") (pin "2") (pinfunction "2_2") (pintype "passive"))
      (node (ref "S248") (pin "2") (pinfunction "2_2") (pintype "passive"))
      (node (ref "S249") (pin "2") (pinfunction "2_2") (pintype "passive"))
      (node (ref "S250") (pin "2") (pinfunction "2_2") (pintype "passive"))
      (node (ref "S264") (pin "1") (pinfunction "1_1") (pintype "passive"))
      (node (ref "S264_1") (pin "1") (pinfunction "1_1") (pintype "passive"))
      (node (ref "S279") (pin "2") (pinfunction "2_2") (pintype "passive"))
      (node (ref "S289") (pin "2") (pinfunction "2_2") (pintype "passive"))
    )
    (net (code "9") (name "/row1") (class "Default")
      (node (ref "D201") (pin "2") (pinfunction "K_2") (pintype "passive"))
      (node (ref "D202") (pin "2") (pinfunction "K_2") (pintype "passive"))
      (node (ref "D204") (pin "2") (pinfunction "K_2") (pintype "passive"))
      (node (ref "D206") (pin "2") (pinfunction "K_2") (pintype "passive"))
      (node (ref "D208") (pin "2") (pinfunction "K_2") (pintype "passive"))
      (node (ref "D210") (pin "2") (pinfunction "K_2") (pintype "passive"))
      (node (ref "D212") (pin "2") (pinfunction "K_2") (pintype "passive"))
      (node (ref "D214") (pin "2") (pinfunction "K_2") (pintype "passive"))
    )
    (net (code "10") (name "/row2") (class "Default")
      (node (ref "D203") (pin "2") (pinfunction "K_2") (pintype "passive"))
      (node (ref "D205") (pin "2") (pinfunction "K_2") (pintype "passive"))
      (node (ref "D207") (pin "2") (pinfunction "K_2") (pintype "passive"))
      (node (ref "D209") (pin "2") (pinfunction "K_2") (pintype "passive"))
      (node (ref "D211") (pin "2") (pinfunction "K_2") (pintype "passive"))
      (node (ref "D213") (pin "2") (pinfunction "K_2") (pintype "passive"))
      (node (ref "D215") (pin "2") (pinfunction "K_2") (pintype "passive"))
      (node (ref "D290") (pin "2") (pinfunction "K_2") (pintype "passive"))
    )
    (net (code "11") (name "/row3") (class "Default")
      (node (ref "D217") (pin "2") (pinfunction "K_2") (pintype "passive"))
      (node (ref "D219") (pin "2") (pinfunction "K_2") (pintype "passive"))
      (node (ref "D221") (pin "2") (pinfunction "K_2") (pintype "passive"))
      (node (ref "D223") (pin "2") (pinfunction "K_2") (pintype "passive"))
      (node (ref "D225") (pin "2") (pinfunction "K_2") (pintype "passive"))
      (node (ref "D227") (pin "2") (pinfunction "K_2") (pintype "passive"))
      (node (ref "D229") (pin "2") (pinfunction "K_2") (pintype "passive"))
      (node (ref "D231") (pin "2") (pinfunction "K_2") (pintype "passive"))
    )
    (net (code "12") (name "/row4") (class "Default")
      (node (ref "D216") (pin "2") (pinfunction "K_2") (pintype "passive"))
      (node (ref "D218") (pin "2") (pinfunction "K_2") (pintype "passive"))
      (node (ref "D220") (pin "2") (pinfunction "K_2") (pintype "passive"))
      (node (ref "D222") (pin "2") (pinfunction "K_2") (pintype "passive"))
      (node (ref "D224") (pin "2") (pinfunction "K_2") (pintype "passive"))
      (node (ref "D226") (pin "2") (pinfunction "K_2") (pintype "passive"))
      (node (ref "D228") (pin "2") (pinfunction "K_2") (pintype "passive"))
      (node (ref "D230") (pin "2") (pinfunction "K_2") (pintype "passive"))
    )
    (net (code "13") (name "/row5") (class "Default")
      (node (ref "D234") (pin "2") (pinfunction "K_2") (pintype "passive"))
      (node (ref "D236") (pin "2") (pinfunction "K_2") (pintype "passive"))
      (node (ref "D238") (pin "2") (pinfunction "K_2") (pintype "passive"))
      (node (ref "D240") (pin "2") (pinfunction "K_2") (pintype "passive"))
      (node (ref "D242") (pin "2") (pinfunction "K_2") (pintype "passive"))
      (node (ref "D244") (pin "2") (pinfunction "K_2") (pintype "passive"))
      (node (ref "D246") (pin "2") (pinfunction "K_2") (pintype "passive"))
      (node (ref "D248") (pin "2") (pinfunction "K_2") (pintype "passive"))
    )
    (net (code "14") (name "/row6") (class "Default")
      (node (ref "D232") (pin "2") (pinfunction "K_2") (pintype "passive"))
      (node (ref "D235") (pin "2") (pinfunction "K_2") (pintype "passive"))
      (node (ref "D237") (pin "2") (pinfunction "K_2") (pintype "passive"))
      (node (ref "D239") (pin "2") (pinfunction "K_2") (pintype "passive"))
      (node (ref "D241") (pin "2") (pinfunction "K_2") (pintype "passive"))
      (node (ref "D243") (pin "2") (pinfunction "K_2") (pintype "passive"))
      (node (ref "D245") (pin "2") (pinfunction "K_2") (pintype "passive"))
      (node (ref "D247") (pin "2") (pinfunction "K_2") (pintype "passive"))
    )
    (net (code "15") (name "/row7") (class "Default")
      (node (ref "D251") (pin "2") (pinfunction "K_2") (pintype "passive"))
      (node (ref "D253") (pin "2") (pinfunction "K_2") (pintype "passive"))
      (node (ref "D255") (pin "2") (pinfunction "K_2") (pintype "passive"))
      (node (ref "D257") (pin "2") (pinfunction "K_2") (pintype "passive"))
      (node (ref "D259") (pin "2") (pinfunction "K_2") (pintype "passive"))
      (node (ref "D261") (pin "2") (pinfunction "K_2") (pintype "passive"))
      (node (ref "D263") (pin "2") (pinfunction "K_2") (pintype "passive"))
      (node (ref "D264") (pin "2") (pinfunction "K_2") (pintype "passive"))
    )
    (net (code "16") (name "/row8") (class "Default")
      (node (ref "D249") (pin "2") (pinfunction "K_2") (pintype "passive"))
      (node (ref "D252") (pin "2") (pinfunction "K_2") (pintype "passive"))
      (node (ref "D254") (pin "2") (pinfunction "K_2") (pintype "passive"))
      (node (ref "D256") (pin "2") (pinfunction "K_2") (pintype "passive"))
      (node (ref "D258") (pin "2") (pinfunction "K_2") (pintype "passive"))
      (node (ref "D260") (pin "2") (pinfunction "K_2") (pintype "passive"))
      (node (ref "D262") (pin "2") (pinfunction "K_2") (pintype "passive"))
      (node (ref "D296") (pin "2") (pinfunction "K_2") (pintype "passive"))
    )
    (net (code "17") (name "/row9") (class "Default")
      (node (ref "D265") (pin "2") (pinfunction "K_2") (pintype "passive"))
      (node (ref "D267") (pin "2") (pinfunction "K_2") (pintype "passive"))
      (node (ref "D269") (pin "2") (pinfunction "K_2") (pintype "passive"))
      (node (ref "D271") (pin "2") (pinfunction "K_2") (pintype "passive"))
      (node (ref "D273") (pin "2") (pinfunction "K_2") (pintype "passive"))
      (node (ref "D275") (pin "2") (pinfunction "K_2") (pintype "passive"))
      (node (ref "D277") (pin "2") (pinfunction "K_2") (pintype "passive"))
      (node (ref "D279") (pin "2") (pinfunction "K_2") (pintype "passive"))
    )
    (net (code "18") (name "/row10") (class "Default")
      (node (ref "D233") (pin "2") (pinfunction "K_2") (pintype "passive"))
      (node (ref "D266") (pin "2") (pinfunction "K_2") (pintype "passive"))
      (node (ref "D268") (pin "2") (pinfunction "K_2") (pintype "passive"))
      (node (ref "D270") (pin "2") (pinfunction "K_2") (pintype "passive"))
      (node (ref "D272") (pin "2") (pinfunction "K_2") (pintype "passive"))
      (node (ref "D274") (pin "2") (pinfunction "K_2") (pintype "passive"))
      (node (ref "D276") (pin "2") (pinfunction "K_2") (pintype "passive"))
      (node (ref "D278") (pin "2") (pinfunction "K_2") (pintype "passive"))
    )
    (net (code "19") (name "/row11") (class "Default")
      (node (ref "D280") (pin "2") (pinfunction "K_2") (pintype "passive"))
      (node (ref "D282") (pin "2") (pinfunction "K_2") (pintype "passive"))
      (node (ref "D283") (pin "2") (pinfunction "K_2") (pintype "passive"))
      (node (ref "D285") (pin "2") (pinfunction "K_2") (pintype "passive"))
      (node (ref "D287") (pin "2") (pinfunction "K_2") (pintype "passive"))
      (node (ref "D289") (pin "2") (pinfunction "K_2") (pintype "passive"))
      (node (ref "D293") (pin "2") (pinfunction "K_2") (pintype "passive"))
    )
    (net (code "20") (name "/row12") (class "Default")
      (node (ref "D250") (pin "2") (pinfunction "K_2") (pintype "passive"))
      (node (ref "D281") (pin "2") (pinfunction "K_2") (pintype "passive"))
      (node (ref "D284") (pin "2") (pinfunction "K_2") (pintype "passive"))
      (node (ref "D286") (pin "2") (pinfunction "K_2") (pintype "passive"))
      (node (ref "D288") (pin "2") (pinfunction "K_2") (pintype "passive"))
      (node (ref "D294") (pin "2") (pinfunction "K_2") (pintype "passive"))
      (node (ref "D295") (pin "2") (pinfunction "K_2") (pintype "passive"))
    )
    (net (code "21") (name "Net-(D201-A)") (class "Default")
      (node (ref "D201") (pin "1") (pinfunction "A_1") (pintype "passive"))
      (node (ref "S201") (pin "1") (pinfunction "1_1") (pintype "passive"))
    )
    (net (code "22") (name "Net-(D202-A)") (class "Default")
      (node (ref "D202") (pin "1") (pinfunction "A_1") (pintype "passive"))
      (node (ref "S202") (pin "1") (pinfunction "1_1") (pintype "passive"))
    )
    (net (code "23") (name "Net-(D203-A)") (class "Default")
      (node (ref "D203") (pin "1") (pinfunction "A_1") (pintype "passive"))
      (node (ref "S203") (pin "1") (pinfunction "1_1") (pintype "passive"))
    )
    (net (code "24") (name "Net-(D204-A)") (class "Default")
      (node (ref "D204") (pin "1") (pinfunction "A_1") (pintype "passive"))
      (node (ref "S204") (pin "1") (pinfunction "1_1") (pintype "passive"))
    )
    (net (code "25") (name "Net-(D205-A)") (class "Default")
      (node (ref "D205") (pin "1") (pinfunction "A_1") (pintype "passive"))
      (node (ref "S205") (pin "1") (pinfunction "1_1") (pintype "passive"))
    )
    (net (code "26") (name "Net-(D206-A)") (class "Default")
      (node (ref "D206") (pin "1") (pinfunction "A_1") (pintype "passive"))
      (node (ref "S206") (pin "1") (pinfunction "1_1") (pintype "passive"))
    )
    (net (code "27") (name "Net-(D207-A)") (class "Default")
      (node (ref "D207") (pin "1") (pinfunction "A_1") (pintype "passive"))
      (node (ref "S207") (pin "1") (pinfunction "1_1") (pintype "passive"))
    )
    (net (code "28") (name "Net-(D208-A)") (class "Default")
      (node (ref "D208") (pin "1") (pinfunction "A_1") (pintype "passive"))
      (node (ref "S208") (pin "1") (pinfunction "1_1") (pintype "passive"))
    )
    (net (code "29") (name "Net-(D209-A)") (class "Default")
      (node (ref "D209") (pin "1") (pinfunction "A_1") (pintype "passive"))
      (node (ref "S209") (pin "1") (pinfunction "1_1") (pintype "passive"))
    )
    (net (code "30") (name "Net-(D210-A)") (class "Default")
      (node (ref "D210") (pin "1") (pinfunction "A_1") (pintype "passive"))
      (node (ref "S210") (pin "1") (pinfunction "1_1") (pintype "passive"))
    )
    (net (code "31") (name "Net-(D211-A)") (class "Default")
      (node (ref "D211") (pin "1") (pinfunction "A_1") (pintype "passive"))
      (node (ref "S211") (pin "1") (pinfunction "1_1") (pintype "passive"))
    )
    (net (code "32") (name "Net-(D212-A)") (class "Default")
      (node (ref "D212") (pin "1") (pinfunction "A_1") (pintype "passive"))
      (node (ref "S212") (pin "1") (pinfunction "1_1") (pintype "passive"))
    )
    (net (code "33") (name "Net-(D213-A)") (class "Default")
      (node (ref "D213") (pin "1") (pinfunction "A_1") (pintype "passive"))
      (node (ref "S213") (pin "1") (pinfunction "1_1") (pintype "passive"))
    )
    (net (code "34") (name "Net-(D214-A)") (class "Default")
      (node (ref "D214") (pin "1") (pinfunction "A_1") (pintype "passive"))
      (node (ref "S214") (pin "1") (pinfunction "1_1") (pintype "passive"))
    )
    (net (code "35") (name "Net-(D215-A)") (class "Default")
      (node (ref "D215") (pin "1") (pinfunction "A_1") (pintype "passive"))
      (node (ref "S215") (pin "1") (pinfunction "1_1") (pintype "passive"))
    )
    (net (code "36") (name "Net-(D216-A)") (class "Default")
      (node (ref "D216") (pin "1") (pinfunction "A_1") (pintype "passive"))
      (node (ref "S216") (pin "1") (pinfunction "1_1") (pintype "passive"))
    )
    (net (code "37") (name "Net-(D217-A)") (class "Default")
      (node (ref "D217") (pin "1") (pinfunction "A_1") (pintype "passive"))
      (node (ref "S217") (pin "1") (pinfunction "1_1") (pintype "passive"))
    )
    (net (code "38") (name "Net-(D218-A)") (class "Default")
      (node (ref "D218") (pin "1") (pinfunction "A_1") (pintype "passive"))
      (node (ref "S218") (pin "1") (pinfunction "1_1") (pintype "passive"))
    )
    (net (code "39") (name "Net-(D219-A)") (class "Default")
      (node (ref "D219") (pin "1") (pinfunction "A_1") (pintype "passive"))
      (node (ref "S219") (pin "1") (pinfunction "1_1") (pintype "passive"))
    )
    (net (code "40") (name "Net-(D220-A)") (class "Default")
      (node (ref "D220") (pin "1") (pinfunction "A_1") (pintype "passive"))
      (node (ref "S220") (pin "1") (pinfunction "1_1") (pintype "passive"))
    )
    (net (code "41") (name "Net-(D221-A)") (class "Default")
      (node (ref "D221") (pin "1") (pinfunction "A_1") (pintype "passive"))
      (node (ref "S221") (pin "1") (pinfunction "1_1") (pintype "passive"))
    )
    (net (code "42") (name "Net-(D222-A)") (class "Default")
      (node (ref "D222") (pin "1") (pinfunction "A_1") (pintype "passive"))
      (node (ref "S222") (pin "1") (pinfunction "1_1") (pintype "passive"))
    )
    (net (code "43") (name "Net-(D223-A)") (class "Default")
      (node (ref "D223") (pin "1") (pinfunction "A_1") (pintype "passive"))
      (node (ref "S223") (pin "1") (pinfunction "1_1") (pintype "passive"))
    )
    (net (code "44") (name "Net-(D224-A)") (class "Default")
      (node (ref "D224") (pin "1") (pinfunction "A_1") (pintype "passive"))
      (node (ref "S224") (pin "1") (pinfunction "1_1") (pintype "passive"))
    )
    (net (code "45") (name "Net-(D225-A)") (class "Default")
      (node (ref "D225") (pin "1") (pinfunction "A_1") (pintype "passive"))
      (node (ref "S225") (pin "1") (pinfunction "1_1") (pintype "passive"))
    )
    (net (code "46") (name "Net-(D226-A)") (class "Default")
      (node (ref "D226") (pin "1") (pinfunction "A_1") (pintype "passive"))
      (node (ref "S226") (pin "1") (pinfunction "1_1") (pintype "passive"))
    )
    (net (code "47") (name "Net-(D227-A)") (class "Default")
      (node (ref "D227") (pin "1") (pinfunction "A_1") (pintype "passive"))
      (node (ref "S227") (pin "1") (pinfunction "1_1") (pintype "passive"))
    )
    (net (code "48") (name "Net-(D228-A)") (class "Default")
      (node (ref "D228") (pin "1") (pinfunction "A_1") (pintype "passive"))
      (node (ref "S228") (pin "1") (pinfunction "1_1") (pintype "passive"))
    )
    (net (code "49") (name "Net-(D229-A)") (class "Default")
      (node (ref "D229") (pin "1") (pinfunction "A_1") (pintype "passive"))
      (node (ref "S229") (pin "1") (pinfunction "1_1") (pintype "passive"))
    )
    (net (code "50") (name "Net-(D230-A)") (class "Default")
      (node (ref "D230") (pin "1") (pinfunction "A_1") (pintype "passive"))
      (node (ref "S230") (pin "1") (pinfunction "1_1") (pintype "passive"))
    )
    (net (code "51") (name "Net-(D231-A)") (class "Default")
      (node (ref "D231") (pin "1") (pinfunction "A_1") (pintype "passive"))
      (node (ref "S231") (pin "1") (pinfunction "1_1") (pintype "passive"))
    )
    (net (code "52") (name "Net-(D232-A)") (class "Default")
      (node (ref "D232") (pin "1") (pinfunction "A_1") (pintype "passive"))
      (node (ref "S232") (pin "1") (pinfunction "1_1") (pintype "passive"))
    )
    (net (code "53") (name "Net-(D233-A)") (class "Default")
      (node (ref "D233") (pin "1") (pinfunction "A_1") (pintype "passive"))
      (node (ref "S233") (pin "1") (pinfunction "1_1") (pintype "passive"))
    )
    (net (code "54") (name "Net-(D234-A)") (class "Default")
      (node (ref "D234") (pin "1") (pinfunction "A_1") (pintype "passive"))
      (node (ref "S234") (pin "1") (pinfunction "1_1") (pintype "passive"))
    )
    (net (code "55") (name "Net-(D235-A)") (class "Default")
      (node (ref "D235") (pin "1") (pinfunction "A_1") (pintype "passive"))
      (node (ref "S235") (pin "1") (pinfunction "1_1") (pintype "passive"))
    )
    (net (code "56") (name "Net-(D236-A)") (class "Default")
      (node (ref "D236") (pin "1") (pinfunction "A_1") (pintype "passive"))
      (node (ref "S236") (pin "1") (pinfunction "1_1") (pintype "passive"))
    )
    (net (code "57") (name "Net-(D237-A)") (class "Default")
      (node (ref "D237") (pin "1") (pinfunction "A_1") (pintype "passive"))
      (node (ref "S237") (pin "1") (pinfunction "1_1") (pintype "passive"))
    )
    (net (code "58") (name "Net-(D238-A)") (class "Default")
      (node (ref "D238") (pin "1") (pinfunction "A_1") (pintype "passive"))
      (node (ref "S238") (pin "1") (pinfunction "1_1") (pintype "passive"))
    )
    (net (code "59") (name "Net-(D239-A)") (class "Default")
      (node (ref "D239") (pin "1") (pinfunction "A_1") (pintype "passive"))
      (node (ref "S239") (pin "1") (pinfunction "1_1") (pintype "passive"))
    )
    (net (code "60") (name "Net-(D240-A)") (class "Default")
      (node (ref "D240") (pin "1") (pinfunction "A_1") (pintype "passive"))
      (node (ref "S240") (pin "1") (pinfunction "1_1") (pintype "passive"))
    )
    (net (code "61") (name "Net-(D241-A)") (class "Default")
      (node (ref "D241") (pin "1") (pinfunction "A_1") (pintype "passive"))
      (node (ref "S241") (pin "1") (pinfunction "1_1") (pintype "passive"))
    )
    (net (code "62") (name "Net-(D242-A)") (class "Default")
      (node (ref "D242") (pin "1") (pinfunction "A_1") (pintype "passive"))
      (node (ref "S242") (pin "1") (pinfunction "1_1") (pintype "passive"))
    )
    (net (code "63") (name "Net-(D243-A)") (class "Default")
      (node (ref "D243") (pin "1") (pinfunction "A_1") (pintype "passive"))
      (node (ref "S243") (pin "1") (pinfunction "1_1") (pintype "passive"))
    )
    (net (code "64") (name "Net-(D244-A)") (class "Default")
      (node (ref "D244") (pin "1") (pinfunction "A_1") (pintype "passive"))
      (node (ref "S244") (pin "1") (pinfunction "1_1") (pintype "passive"))
    )
    (net (code "65") (name "Net-(D245-A)") (class "Default")
      (node (ref "D245") (pin "1") (pinfunction "A_1") (pintype "passive"))
      (node (ref "S245") (pin "1") (pinfunction "1_1") (pintype "passive"))
    )
    (net (code "66") (name "Net-(D246-A)") (class "Default")
      (node (ref "D246") (pin "1") (pinfunction "A_1") (pintype "passive"))
      (node (ref "S246") (pin "1") (pinfunction "1_1") (pintype "passive"))
    )
    (net (code "67") (name "Net-(D247-A)") (class "Default")
      (node (ref "D247") (pin "1") (pinfunction "A_1") (pintype "passive"))
      (node (ref "S247") (pin "1") (pinfunction "1_1") (pintype "passive"))
    )
    (net (code "68") (name "Net-(D248-A)") (class "Default")
      (node (ref "D248") (pin "1") (pinfunction "A_1") (pintype "passive"))
      (node (ref "S248") (pin "1") (pinfunction "1_1") (pintype "passive"))
    )
    (net (code "69") (name "Net-(D249-A)") (class "Default")
      (node (ref "D249") (pin "1") (pinfunction "A_1") (pintype "passive"))
      (node (ref "S249") (pin "1") (pinfunction "1_1") (pintype "passive"))
    )
    (net (code "70") (name "Net-(D250-A)") (class "Default")
      (node (ref "D250") (pin "1") (pinfunction "A_1") (pintype "passive"))
      (node (ref "S250") (pin "1") (pinfunction "1_1") (pintype "passive"))
    )
    (net (code "71") (name "Net-(D251-A)") (class "Default")
      (node (ref "D251") (pin "1") (pinfunction "A_1") (pintype "passive"))
      (node (ref "S251") (pin "1") (pinfunction "1_1") (pintype "passive"))
    )
    (net (code "72") (name "Net-(D252-A)") (class "Default")
      (node (ref "D252") (pin "1") (pinfunction "A_1") (pintype "passive"))
      (node (ref "S252") (pin "1") (pinfunction "1_1") (pintype "passive"))
    )
    (net (code "73") (name "Net-(D253-A)") (class "Default")
      (node (ref "D253") (pin "1") (pinfunction "A_1") (pintype "passive"))
      (node (ref "S253") (pin "1") (pinfunction "1_1") (pintype "passive"))
    )
    (net (code "74") (name "Net-(D254-A)") (class "Default")
      (node (ref "D254") (pin "1") (pinfunction "A_1") (pintype "passive"))
      (node (ref "S254") (pin "1") (pinfunction "1_1") (pintype "passive"))
    )
    (net (code "75") (name "Net-(D255-A)") (class "Default")
      (node (ref "D255") (pin "1") (pinfunction "A_1") (pintype "passive"))
      (node (ref "S255") (pin "1") (pinfunction "1_1") (pintype "passive"))
    )
    (net (code "76") (name "Net-(D256-A)") (class "Default")
      (node (ref "D256") (pin "1") (pinfunction "A_1") (pintype "passive"))
      (node (ref "S256") (pin "1") (pinfunction "1_1") (pintype "passive"))
    )
    (net (code "77") (name "Net-(D257-A)") (class "Default")
      (node (ref "D257") (pin "1") (pinfunction "A_1") (pintype "passive"))
      (node (ref "S257") (pin "1") (pinfunction "1_1") (pintype "passive"))
    )
    (net (code "78") (name "Net-(D258-A)") (class "Default")
      (node (ref "D258") (pin "1") (pinfunction "A_1") (pintype "passive"))
      (node (ref "S258") (pin "1") (pinfunction "1_1") (pintype "passive"))
    )
    (net (code "79") (name "Net-(D259-A)") (class "Default")
      (node (ref "D259") (pin "1") (pinfunction "A_1") (pintype "passive"))
      (node (ref "S259") (pin "1") (pinfunction "1_1") (pintype "passive"))
    )
    (net (code "80") (name "Net-(D260-A)") (class "Default")
      (node (ref "D260") (pin "1") (pinfunction "A_1") (pintype "passive"))
      (node (ref "S260") (pin "1") (pinfunction "1_1") (pintype "passive"))
    )
    (net (code "81") (name "Net-(D261-A)") (class "Default")
      (node (ref "D261") (pin "1") (pinfunction "A_1") (pintype "passive"))
      (node (ref "S261") (pin "1") (pinfunction "1_1") (pintype "passive"))
    )
    (net (code "82") (name "Net-(D262-A)") (class "Default")
      (node (ref "D262") (pin "1") (pinfunction "A_1") (pintype "passive"))
      (node (ref "S262") (pin "1") (pinfunction "1_1") (pintype "passive"))
    )
    (net (code "83") (name "Net-(D263-A)") (class "Default")
      (node (ref "D263") (pin "1") (pinfunction "A_1") (pintype "passive"))
      (node (ref "S263") (pin "1") (pinfunction "1_1") (pintype "passive"))
    )
    (net (code "84") (name "Net-(D264-A)") (class "Default")
      (node (ref "D264") (pin "1") (pinfunction "A_1") (pintype "passive"))
      (node (ref "S264") (pin "2") (pinfunction "2_2") (pintype "passive"))
      (node (ref "S264_1") (pin "2") (pinfunction "2_2") (pintype "passive"))
    )
    (net (code "85") (name "Net-(D265-A)") (class "Default")
      (node (ref "D265") (pin "1") (pinfunction "A_1") (pintype "passive"))
      (node (ref "S265") (pin "1") (pinfunction "1_1") (pintype "passive"))
      (node (ref "S265_1") (pin "1") (pinfunction "1_1") (pintype "passive"))
    )
    (net (code "86") (name "Net-(D266-A)") (class "Default")
      (node (ref "D266") (pin "1") (pinfunction "A_1") (pintype "passive"))
      (node (ref "S266") (pin "1") (pinfunction "1_1") (pintype "passive"))
    )
    (net (code "87") (name "Net-(D267-A)") (class "Default")
      (node (ref "D267") (pin "1") (pinfunction "A_1") (pintype "passive"))
      (node (ref "S267") (pin "1") (pinfunction "1_1") (pintype "passive"))
    )
    (net (code "88") (name "Net-(D268-A)") (class "Default")
      (node (ref "D268") (pin "1") (pinfunction "A_1") (pintype "passive"))
      (node (ref "S268") (pin "1") (pinfunction "1_1") (pintype "passive"))
    )
    (net (code "89") (name "Net-(D269-A)") (class "Default")
      (node (ref "D269") (pin "1") (pinfunction "A_1") (pintype "passive"))
      (node (ref "S269") (pin "1") (pinfunction "1_1") (pintype "passive"))
    )
    (net (code "90") (name "Net-(D270-A)") (class "Default")
      (node (ref "D270") (pin "1") (pinfunction "A_1") (pintype "passive"))
      (node (ref "S270") (pin "1") (pinfunction "1_1") (pintype "passive"))
    )
    (net (code "91") (name "Net-(D271-A)") (class "Default")
      (node (ref "D271") (pin "1") (pinfunction "A_1") (pintype "passive"))
      (node (ref "S271") (pin "1") (pinfunction "1_1") (pintype "passive"))
    )
    (net (code "92") (name "Net-(D272-A)") (class "Default")
      (node (ref "D272") (pin "1") (pinfunction "A_1") (pintype "passive"))
      (node (ref "S272") (pin "1") (pinfunction "1_1") (pintype "passive"))
    )
    (net (code "93") (name "Net-(D273-A)") (class "Default")
      (node (ref "D273") (pin "1") (pinfunction "A_1") (pintype "passive"))
      (node (ref "S273") (pin "1") (pinfunction "1_1") (pintype "passive"))
    )
    (net (code "94") (name "Net-(D274-A)") (class "Default")
      (node (ref "D274") (pin "1") (pinfunction "A_1") (pintype "passive"))
      (node (ref "S274") (pin "1") (pinfunction "1_1") (pintype "passive"))
    )
    (net (code "95") (name "Net-(D275-A)") (class "Default")
      (node (ref "D275") (pin "1") (pinfunction "A_1") (pintype "passive"))
      (node (ref "S275") (pin "1") (pinfunction "1_1") (pintype "passive"))
    )
    (net (code "96") (name "Net-(D276-A)") (class "Default")
      (node (ref "D276") (pin "1") (pinfunction "A_1") (pintype "passive"))
      (node (ref "S276") (pin "1") (pinfunction "1_1") (pintype "passive"))
    )
    (net (code "97") (name "Net-(D277-A)") (class "Default")
      (node (ref "D277") (pin "1") (pinfunction "A_1") (pintype "passive"))
      (node (ref "S277") (pin "1") (pinfunction "1_1") (pintype "passive"))
      (node (ref "S277_1") (pin "1") (pinfunction "1_1") (pintype "passive"))
    )
    (net (code "98") (name "Net-(D278-A)") (class "Default")
      (node (ref "D278") (pin "1") (pinfunction "A_1") (pintype "passive"))
      (node (ref "S278") (pin "1") (pinfunction "1_1") (pintype "passive"))
    )
    (net (code "99") (name "Net-(D279-A)") (class "Default")
      (node (ref "D279") (pin "1") (pinfunction "A_1") (pintype "passive"))
      (node (ref "S279") (pin "1") (pinfunction "1_1") (pintype "passive"))
    )
    (net (code "100") (name "Net-(D280-A)") (class "Default")
      (node (ref "D280") (pin "1") (pinfunction "A_1") (pintype "passive"))
      (node (ref "S280") (pin "2") (pinfunction "2_2") (pintype "passive"))
    )
    (net (code "101") (name "Net-(D281-A)") (class "Default")
      (node (ref "D281") (pin "1") (pinfunction "A_1") (pintype "passive"))
      (node (ref "S281") (pin "2") (pinfunction "2_2") (pintype "passive"))
    )
    (net (code "102") (name "Net-(D282-A)") (class "Default")
      (node (ref "D282") (pin "1") (pinfunction "A_1") (pintype "passive"))
      (node (ref "S282") (pin "2") (pinfunction "2_2") (pintype "passive"))
    )
    (net (code "103") (name "Net-(D283-A)") (class "Default")
      (node (ref "D283") (pin "1") (pinfunction "A_1") (pintype "passive"))
      (node (ref "S283") (pin "1") (pinfunction "1_1") (pintype "passive"))
      (node (ref "S283_1") (pin "1") (pinfunction "1_1") (pintype "passive"))
      (node (ref "S283_2") (pin "1") (pinfunction "1_1") (pintype "passive"))
    )
    (net (code "104") (name "Net-(D284-A)") (class "Default")
      (node (ref "D284") (pin "1") (pinfunction "A_1") (pintype "passive"))
      (node (ref "S284") (pin "1") (pinfunction "1_1") (pintype "passive"))
    )
    (net (code "105") (name "Net-(D285-A)") (class "Default")
      (node (ref "D285") (pin "1") (pinfunction "A_1") (pintype "passive"))
      (node (ref "S285") (pin "1") (pinfunction "1_1") (pintype "passive"))
    )
    (net (code "106") (name "Net-(D286-A)") (class "Default")
      (node (ref "D286") (pin "1") (pinfunction "A_1") (pintype "passive"))
      (node (ref "S286") (pin "1") (pinfunction "1_1") (pintype "passive"))
    )
    (net (code "107") (name "Net-(D287-A)") (class "Default")
      (node (ref "D287") (pin "1") (pinfunction "A_1") (pintype "passive"))
      (node (ref "S287") (pin "1") (pinfunction "1_1") (pintype "passive"))
    )
    (net (code "108") (name "Net-(D288-A)") (class "Default")
      (node (ref "D288") (pin "1") (pinfunction "A_1") (pintype "passive"))
      (node (ref "S288") (pin "1") (pinfunction "1_1") (pintype "passive"))
    )
    (net (code "109") (name "Net-(D289-A)") (class "Default")
      (node (ref "D289") (pin "1") (pinfunction "A_1") (pintype "passive"))
      (node (ref "S289") (pin "1") (pinfunction "1_1") (pintype "passive"))
    )
    (net (code "110") (name "Net-(D290-A)") (class "Default")
      (node (ref "D290") (pin "1") (pinfunction "A_1") (pintype "passive"))
      (node (ref "S290") (pin "1") (pinfunction "1_1") (pintype "passive"))
    )
    (net (code "111") (name "Net-(D293-A)") (class "Default")
      (node (ref "D293") (pin "1") (pinfunction "A_1") (pintype "passive"))
      (node (ref "S293") (pin "1") (pinfunction "1_1") (pintype "passive"))
    )
    (net (code "112") (name "Net-(D294-A)") (class "Default")
      (node (ref "D294") (pin "1") (pinfunction "A_1") (pintype "passive"))
      (node (ref "S294") (pin "2") (pinfunction "2_2") (pintype "passive"))
      (node (ref "S294_2") (pin "1") (pinfunction "1_1") (pintype "passive"))
    )
    (net (code "113") (name "Net-(D295-A)") (class "Default")
      (node (ref "D295") (pin "1") (pinfunction "A_1") (pintype "passive"))
      (node (ref "S295") (pin "2") (pinfunction "2_2") (pintype "passive"))
      (node (ref "S295_2") (pin "1") (pinfunction "1_1") (pintype "passive"))
    )
    (net (code "114") (name "Net-(D296-A)") (class "Default")
      (node (ref "D296") (pin "1") (pinfunction "A_1") (pintype "passive"))
      (node (ref "S296") (pin "1") (pinfunction "1_1") (pintype "passive"))
      (node (ref "S296_1") (pin "1") (pinfunction "1_1") (pintype "passive"))
    )
    (net (code "115") (name "unconnected-(STAB1-Pad1)") (class "Default")
      (node (ref "STAB1") (pin "1") (pinfunction "1_1") (pintype "passive"))
    )
    (net (code "116") (name "unconnected-(STAB2-Pad1)") (class "Default")
      (node (ref "STAB2") (pin "1") (pinfunction "1_1") (pintype "passive"))
    )
    (net (code "117") (name "unconnected-(STAB3-Pad1)") (class "Default")
      (node (ref "STAB3") (pin "1") (pinfunction "1_1") (pintype "passive"))
    )
    (net (code "118") (name "unconnected-(STAB4-Pad1)") (class "Default")
      (node (ref "STAB4") (pin "1") (pinfunction "1_1") (pintype "passive"))
    )
    (net (code "119") (name "unconnected-(STAB5-Pad1)") (class "Default")
      (node (ref "STAB5") (pin "1") (pinfunction "1_1") (pintype "passive"))
    )
    (net (code "120") (name "unconnected-(STAB6-Pad1)") (class "Default")
      (node (ref "STAB6") (pin "1") (pinfunction "1_1") (pintype "passive"))
    )
    (net (code "121") (name "unconnected-(STAB7-Pad1)") (class "Default")
      (node (ref "STAB7") (pin "1") (pinfunction "1_1") (pintype "passive"))
    )
    (net (code "122") (name "unconnected-(STAB8-Pad1)") (class "Default")
      (node (ref "STAB8") (pin "1") (pinfunction "1_1") (pintype "passive"))
    )
    (net (code "123") (name "unconnected-(STAB9-Pad1)") (class "Default")
      (node (ref "STAB9") (pin "1") (pinfunction "1_1") (pintype "passive"))
    )
    (net (code "124") (name "unconnected-(STAB10-Pad1)") (class "Default")
      (node (ref "STAB10") (pin "1") (pinfunction "1_1") (pintype "passive"))
    )
    (net (code "125") (name "unconnected-(STAB11-Pad1)") (class "Default")
      (node (ref "STAB11") (pin "1") (pinfunction "1_1") (pintype "passive"))
    )
  )
)
